# vme_bus_buff.net
KiCad netlist of a schematic drawn in Altium Designer
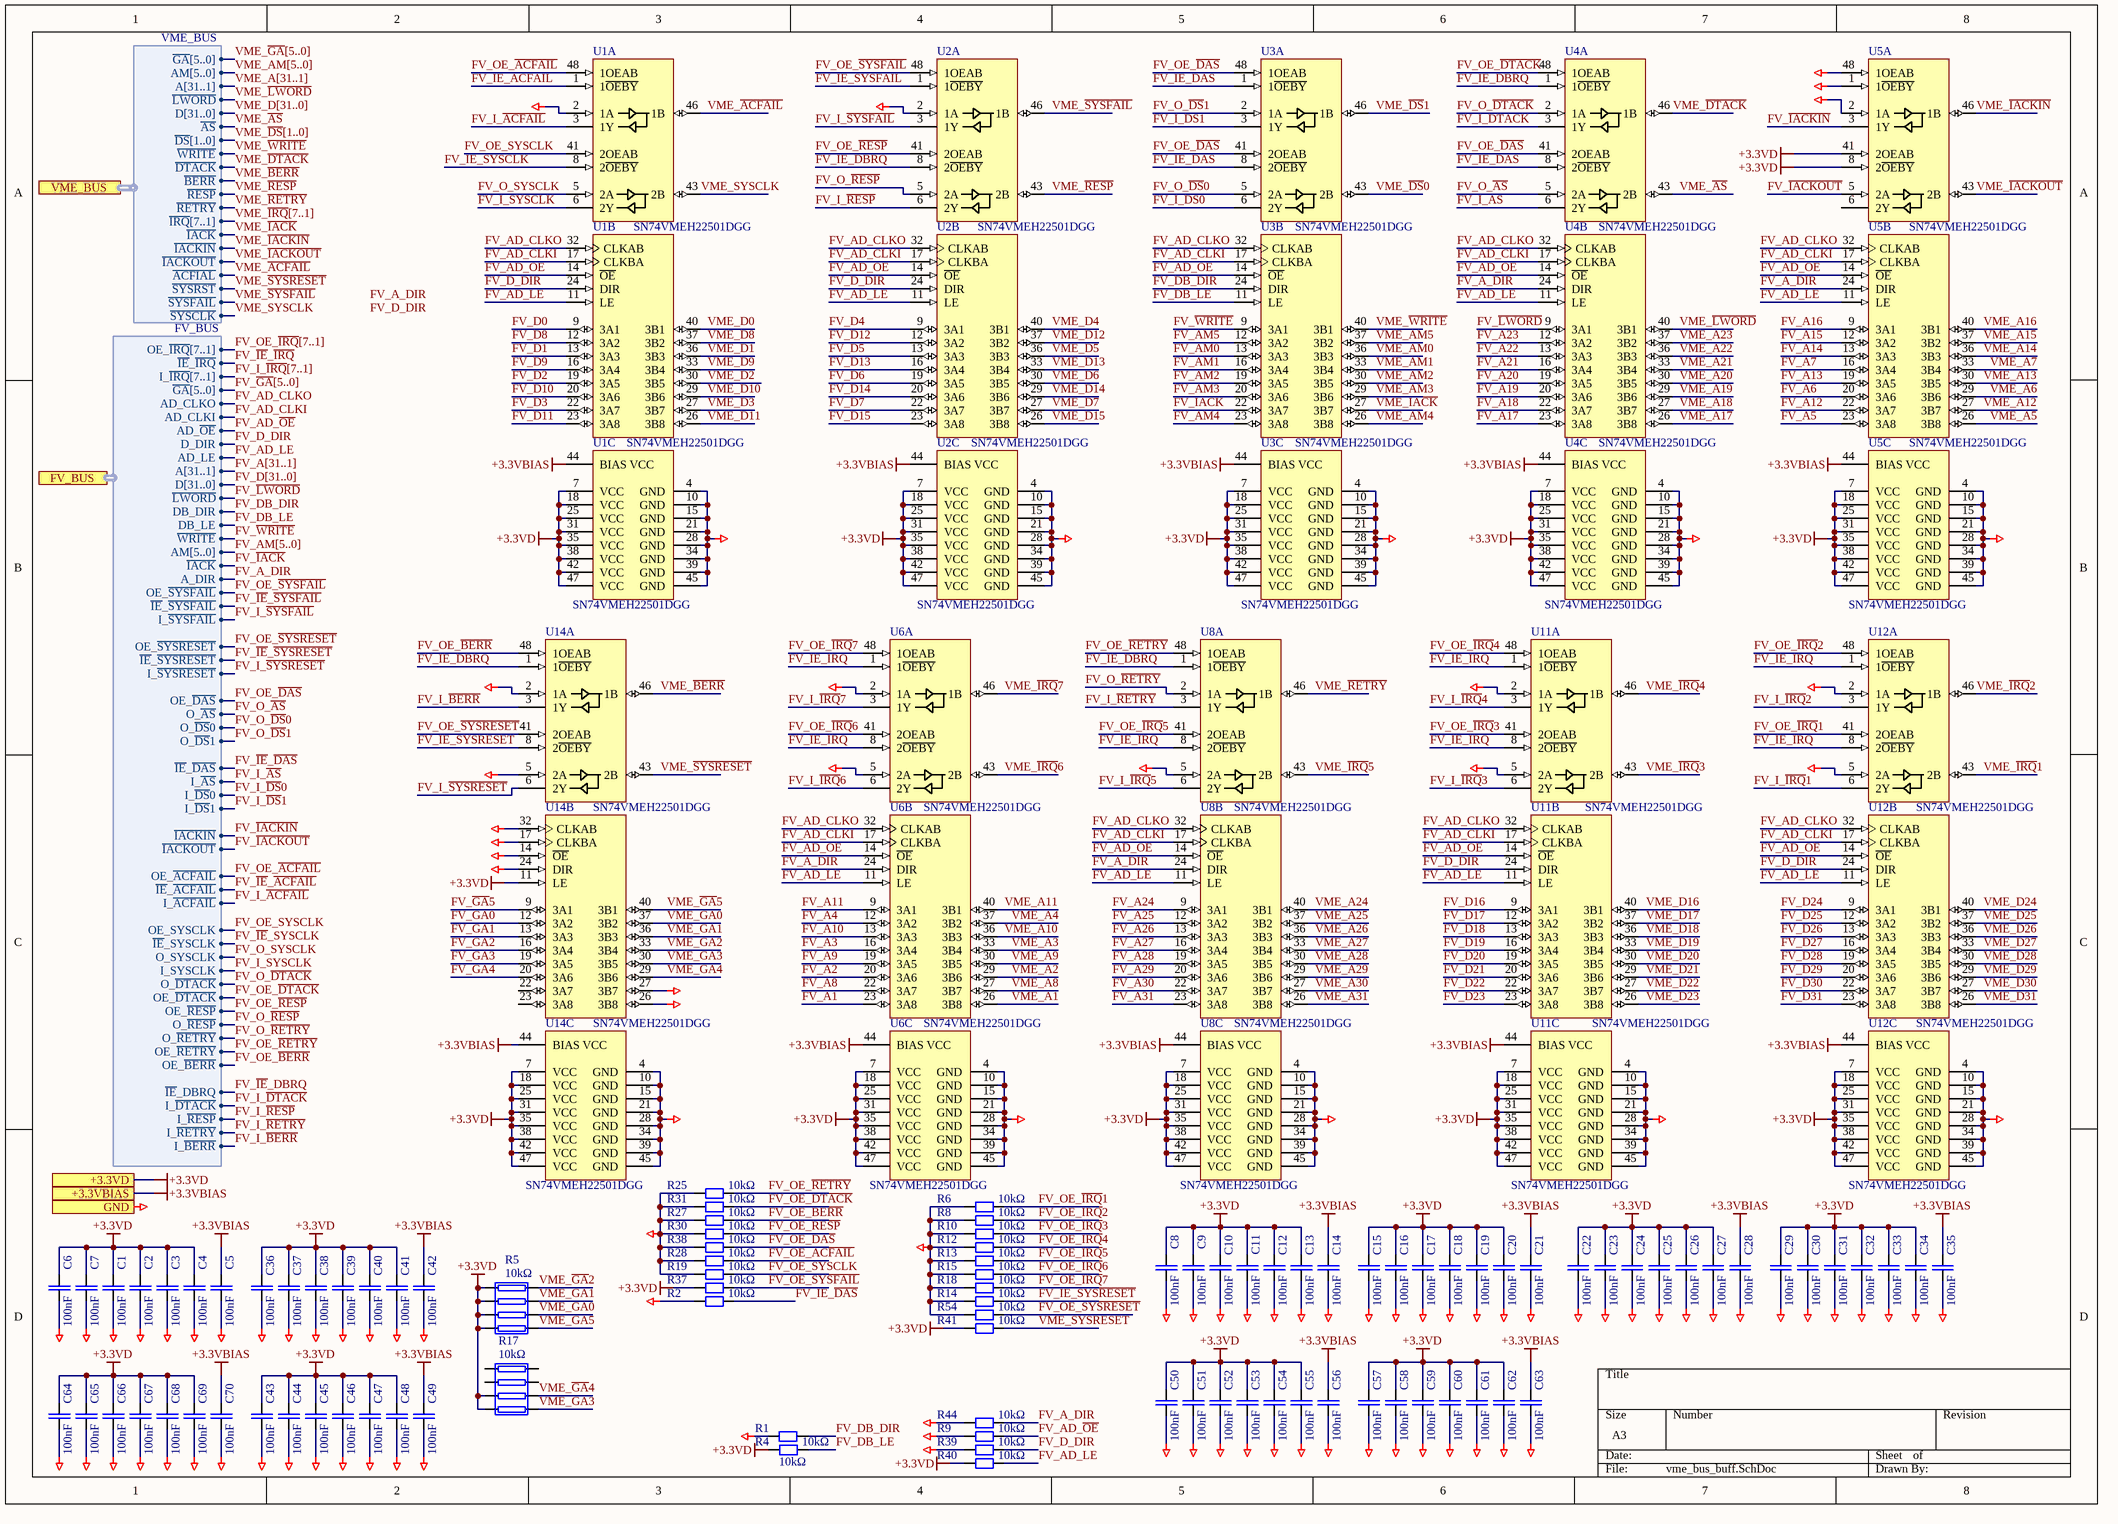
[diagram p0: vme_bus_buff.SchDoc]

(export (version "E")
  (design (tool "Eeschema 10.0.6"))
  (components
    (comp (ref "C1")
      (value "100nF")
      (footprint "CAPC1608N")
      (description "Generic ceramic SMD capacitor")
      (fields (field (name "MAINTAINER") "Evgeniy Kotov"))
      (libsource (lib "[Capacitors] Capacitors SMD") (part "CAPC"))
    )
    (comp (ref "C2")
      (value "100nF")
      (footprint "CAPC1608N")
      (description "Generic ceramic SMD capacitor")
      (fields (field (name "MAINTAINER") "Evgeniy Kotov"))
      (libsource (lib "[Capacitors] Capacitors SMD") (part "CAPC"))
    )
    (comp (ref "C3")
      (value "100nF")
      (footprint "CAPC1608N")
      (description "Generic ceramic SMD capacitor")
      (fields (field (name "MAINTAINER") "Evgeniy Kotov"))
      (libsource (lib "[Capacitors] Capacitors SMD") (part "CAPC"))
    )
    (comp (ref "C4")
      (value "100nF")
      (footprint "CAPC1608N")
      (description "Generic ceramic SMD capacitor")
      (fields (field (name "MAINTAINER") "Evgeniy Kotov"))
      (libsource (lib "[Capacitors] Capacitors SMD") (part "CAPC"))
    )
    (comp (ref "C5")
      (value "100nF")
      (footprint "CAPC1608N")
      (description "Generic ceramic SMD capacitor")
      (fields (field (name "MAINTAINER") "Evgeniy Kotov"))
      (libsource (lib "[Capacitors] Capacitors SMD") (part "CAPC"))
    )
    (comp (ref "C6")
      (value "100nF")
      (footprint "CAPC1608N")
      (description "Generic ceramic SMD capacitor")
      (fields (field (name "MAINTAINER") "Evgeniy Kotov"))
      (libsource (lib "[Capacitors] Capacitors SMD") (part "CAPC"))
    )
    (comp (ref "C7")
      (value "100nF")
      (footprint "CAPC1608N")
      (description "Generic ceramic SMD capacitor")
      (fields (field (name "MAINTAINER") "Evgeniy Kotov"))
      (libsource (lib "[Capacitors] Capacitors SMD") (part "CAPC"))
    )
    (comp (ref "C8")
      (value "100nF")
      (footprint "CAPC1608N")
      (description "Generic ceramic SMD capacitor")
      (fields (field (name "MAINTAINER") "Evgeniy Kotov"))
      (libsource (lib "[Capacitors] Capacitors SMD") (part "CAPC"))
    )
    (comp (ref "C9")
      (value "100nF")
      (footprint "CAPC1608N")
      (description "Generic ceramic SMD capacitor")
      (fields (field (name "MAINTAINER") "Evgeniy Kotov"))
      (libsource (lib "[Capacitors] Capacitors SMD") (part "CAPC"))
    )
    (comp (ref "C10")
      (value "100nF")
      (footprint "CAPC1608N")
      (description "Generic ceramic SMD capacitor")
      (fields (field (name "MAINTAINER") "Evgeniy Kotov"))
      (libsource (lib "[Capacitors] Capacitors SMD") (part "CAPC"))
    )
    (comp (ref "C11")
      (value "100nF")
      (footprint "CAPC1608N")
      (description "Generic ceramic SMD capacitor")
      (fields (field (name "MAINTAINER") "Evgeniy Kotov"))
      (libsource (lib "[Capacitors] Capacitors SMD") (part "CAPC"))
    )
    (comp (ref "C12")
      (value "100nF")
      (footprint "CAPC1608N")
      (description "Generic ceramic SMD capacitor")
      (fields (field (name "MAINTAINER") "Evgeniy Kotov"))
      (libsource (lib "[Capacitors] Capacitors SMD") (part "CAPC"))
    )
    (comp (ref "C13")
      (value "100nF")
      (footprint "CAPC1608N")
      (description "Generic ceramic SMD capacitor")
      (fields (field (name "MAINTAINER") "Evgeniy Kotov"))
      (libsource (lib "[Capacitors] Capacitors SMD") (part "CAPC"))
    )
    (comp (ref "C14")
      (value "100nF")
      (footprint "CAPC1608N")
      (description "Generic ceramic SMD capacitor")
      (fields (field (name "MAINTAINER") "Evgeniy Kotov"))
      (libsource (lib "[Capacitors] Capacitors SMD") (part "CAPC"))
    )
    (comp (ref "C15")
      (value "100nF")
      (footprint "CAPC1608N")
      (description "Generic ceramic SMD capacitor")
      (fields (field (name "MAINTAINER") "Evgeniy Kotov"))
      (libsource (lib "[Capacitors] Capacitors SMD") (part "CAPC"))
    )
    (comp (ref "C16")
      (value "100nF")
      (footprint "CAPC1608N")
      (description "Generic ceramic SMD capacitor")
      (fields (field (name "MAINTAINER") "Evgeniy Kotov"))
      (libsource (lib "[Capacitors] Capacitors SMD") (part "CAPC"))
    )
    (comp (ref "C17")
      (value "100nF")
      (footprint "CAPC1608N")
      (description "Generic ceramic SMD capacitor")
      (fields (field (name "MAINTAINER") "Evgeniy Kotov"))
      (libsource (lib "[Capacitors] Capacitors SMD") (part "CAPC"))
    )
    (comp (ref "C18")
      (value "100nF")
      (footprint "CAPC1608N")
      (description "Generic ceramic SMD capacitor")
      (fields (field (name "MAINTAINER") "Evgeniy Kotov"))
      (libsource (lib "[Capacitors] Capacitors SMD") (part "CAPC"))
    )
    (comp (ref "C19")
      (value "100nF")
      (footprint "CAPC1608N")
      (description "Generic ceramic SMD capacitor")
      (fields (field (name "MAINTAINER") "Evgeniy Kotov"))
      (libsource (lib "[Capacitors] Capacitors SMD") (part "CAPC"))
    )
    (comp (ref "C20")
      (value "100nF")
      (footprint "CAPC1608N")
      (description "Generic ceramic SMD capacitor")
      (fields (field (name "MAINTAINER") "Evgeniy Kotov"))
      (libsource (lib "[Capacitors] Capacitors SMD") (part "CAPC"))
    )
    (comp (ref "C21")
      (value "100nF")
      (footprint "CAPC1608N")
      (description "Generic ceramic SMD capacitor")
      (fields (field (name "MAINTAINER") "Evgeniy Kotov"))
      (libsource (lib "[Capacitors] Capacitors SMD") (part "CAPC"))
    )
    (comp (ref "C22")
      (value "100nF")
      (footprint "CAPC1608N")
      (description "Generic ceramic SMD capacitor")
      (fields (field (name "MAINTAINER") "Evgeniy Kotov"))
      (libsource (lib "[Capacitors] Capacitors SMD") (part "CAPC"))
    )
    (comp (ref "C23")
      (value "100nF")
      (footprint "CAPC1608N")
      (description "Generic ceramic SMD capacitor")
      (fields (field (name "MAINTAINER") "Evgeniy Kotov"))
      (libsource (lib "[Capacitors] Capacitors SMD") (part "CAPC"))
    )
    (comp (ref "C24")
      (value "100nF")
      (footprint "CAPC1608N")
      (description "Generic ceramic SMD capacitor")
      (fields (field (name "MAINTAINER") "Evgeniy Kotov"))
      (libsource (lib "[Capacitors] Capacitors SMD") (part "CAPC"))
    )
    (comp (ref "C25")
      (value "100nF")
      (footprint "CAPC1608N")
      (description "Generic ceramic SMD capacitor")
      (fields (field (name "MAINTAINER") "Evgeniy Kotov"))
      (libsource (lib "[Capacitors] Capacitors SMD") (part "CAPC"))
    )
    (comp (ref "C26")
      (value "100nF")
      (footprint "CAPC1608N")
      (description "Generic ceramic SMD capacitor")
      (fields (field (name "MAINTAINER") "Evgeniy Kotov"))
      (libsource (lib "[Capacitors] Capacitors SMD") (part "CAPC"))
    )
    (comp (ref "C27")
      (value "100nF")
      (footprint "CAPC1608N")
      (description "Generic ceramic SMD capacitor")
      (fields (field (name "MAINTAINER") "Evgeniy Kotov"))
      (libsource (lib "[Capacitors] Capacitors SMD") (part "CAPC"))
    )
    (comp (ref "C28")
      (value "100nF")
      (footprint "CAPC1608N")
      (description "Generic ceramic SMD capacitor")
      (fields (field (name "MAINTAINER") "Evgeniy Kotov"))
      (libsource (lib "[Capacitors] Capacitors SMD") (part "CAPC"))
    )
    (comp (ref "C29")
      (value "100nF")
      (footprint "CAPC1608N")
      (description "Generic ceramic SMD capacitor")
      (fields (field (name "MAINTAINER") "Evgeniy Kotov"))
      (libsource (lib "[Capacitors] Capacitors SMD") (part "CAPC"))
    )
    (comp (ref "C30")
      (value "100nF")
      (footprint "CAPC1608N")
      (description "Generic ceramic SMD capacitor")
      (fields (field (name "MAINTAINER") "Evgeniy Kotov"))
      (libsource (lib "[Capacitors] Capacitors SMD") (part "CAPC"))
    )
    (comp (ref "C31")
      (value "100nF")
      (footprint "CAPC1608N")
      (description "Generic ceramic SMD capacitor")
      (fields (field (name "MAINTAINER") "Evgeniy Kotov"))
      (libsource (lib "[Capacitors] Capacitors SMD") (part "CAPC"))
    )
    (comp (ref "C32")
      (value "100nF")
      (footprint "CAPC1608N")
      (description "Generic ceramic SMD capacitor")
      (fields (field (name "MAINTAINER") "Evgeniy Kotov"))
      (libsource (lib "[Capacitors] Capacitors SMD") (part "CAPC"))
    )
    (comp (ref "C33")
      (value "100nF")
      (footprint "CAPC1608N")
      (description "Generic ceramic SMD capacitor")
      (fields (field (name "MAINTAINER") "Evgeniy Kotov"))
      (libsource (lib "[Capacitors] Capacitors SMD") (part "CAPC"))
    )
    (comp (ref "C34")
      (value "100nF")
      (footprint "CAPC1608N")
      (description "Generic ceramic SMD capacitor")
      (fields (field (name "MAINTAINER") "Evgeniy Kotov"))
      (libsource (lib "[Capacitors] Capacitors SMD") (part "CAPC"))
    )
    (comp (ref "C35")
      (value "100nF")
      (footprint "CAPC1608N")
      (description "Generic ceramic SMD capacitor")
      (fields (field (name "MAINTAINER") "Evgeniy Kotov"))
      (libsource (lib "[Capacitors] Capacitors SMD") (part "CAPC"))
    )
    (comp (ref "C36")
      (value "100nF")
      (footprint "CAPC1608N")
      (description "Generic ceramic SMD capacitor")
      (fields (field (name "MAINTAINER") "Evgeniy Kotov"))
      (libsource (lib "[Capacitors] Capacitors SMD") (part "CAPC"))
    )
    (comp (ref "C37")
      (value "100nF")
      (footprint "CAPC1608N")
      (description "Generic ceramic SMD capacitor")
      (fields (field (name "MAINTAINER") "Evgeniy Kotov"))
      (libsource (lib "[Capacitors] Capacitors SMD") (part "CAPC"))
    )
    (comp (ref "C38")
      (value "100nF")
      (footprint "CAPC1608N")
      (description "Generic ceramic SMD capacitor")
      (fields (field (name "MAINTAINER") "Evgeniy Kotov"))
      (libsource (lib "[Capacitors] Capacitors SMD") (part "CAPC"))
    )
    (comp (ref "C39")
      (value "100nF")
      (footprint "CAPC1608N")
      (description "Generic ceramic SMD capacitor")
      (fields (field (name "MAINTAINER") "Evgeniy Kotov"))
      (libsource (lib "[Capacitors] Capacitors SMD") (part "CAPC"))
    )
    (comp (ref "C40")
      (value "100nF")
      (footprint "CAPC1608N")
      (description "Generic ceramic SMD capacitor")
      (fields (field (name "MAINTAINER") "Evgeniy Kotov"))
      (libsource (lib "[Capacitors] Capacitors SMD") (part "CAPC"))
    )
    (comp (ref "C41")
      (value "100nF")
      (footprint "CAPC1608N")
      (description "Generic ceramic SMD capacitor")
      (fields (field (name "MAINTAINER") "Evgeniy Kotov"))
      (libsource (lib "[Capacitors] Capacitors SMD") (part "CAPC"))
    )
    (comp (ref "C42")
      (value "100nF")
      (footprint "CAPC1608N")
      (description "Generic ceramic SMD capacitor")
      (fields (field (name "MAINTAINER") "Evgeniy Kotov"))
      (libsource (lib "[Capacitors] Capacitors SMD") (part "CAPC"))
    )
    (comp (ref "C43")
      (value "100nF")
      (footprint "CAPC1608N")
      (description "Generic ceramic SMD capacitor")
      (fields (field (name "MAINTAINER") "Evgeniy Kotov"))
      (libsource (lib "[Capacitors] Capacitors SMD") (part "CAPC"))
    )
    (comp (ref "C44")
      (value "100nF")
      (footprint "CAPC1608N")
      (description "Generic ceramic SMD capacitor")
      (fields (field (name "MAINTAINER") "Evgeniy Kotov"))
      (libsource (lib "[Capacitors] Capacitors SMD") (part "CAPC"))
    )
    (comp (ref "C45")
      (value "100nF")
      (footprint "CAPC1608N")
      (description "Generic ceramic SMD capacitor")
      (fields (field (name "MAINTAINER") "Evgeniy Kotov"))
      (libsource (lib "[Capacitors] Capacitors SMD") (part "CAPC"))
    )
    (comp (ref "C46")
      (value "100nF")
      (footprint "CAPC1608N")
      (description "Generic ceramic SMD capacitor")
      (fields (field (name "MAINTAINER") "Evgeniy Kotov"))
      (libsource (lib "[Capacitors] Capacitors SMD") (part "CAPC"))
    )
    (comp (ref "C47")
      (value "100nF")
      (footprint "CAPC1608N")
      (description "Generic ceramic SMD capacitor")
      (fields (field (name "MAINTAINER") "Evgeniy Kotov"))
      (libsource (lib "[Capacitors] Capacitors SMD") (part "CAPC"))
    )
    (comp (ref "C48")
      (value "100nF")
      (footprint "CAPC1608N")
      (description "Generic ceramic SMD capacitor")
      (fields (field (name "MAINTAINER") "Evgeniy Kotov"))
      (libsource (lib "[Capacitors] Capacitors SMD") (part "CAPC"))
    )
    (comp (ref "C49")
      (value "100nF")
      (footprint "CAPC1608N")
      (description "Generic ceramic SMD capacitor")
      (fields (field (name "MAINTAINER") "Evgeniy Kotov"))
      (libsource (lib "[Capacitors] Capacitors SMD") (part "CAPC"))
    )
    (comp (ref "C50")
      (value "100nF")
      (footprint "CAPC1608N")
      (description "Generic ceramic SMD capacitor")
      (fields (field (name "MAINTAINER") "Evgeniy Kotov"))
      (libsource (lib "[Capacitors] Capacitors SMD") (part "CAPC"))
    )
    (comp (ref "C51")
      (value "100nF")
      (footprint "CAPC1608N")
      (description "Generic ceramic SMD capacitor")
      (fields (field (name "MAINTAINER") "Evgeniy Kotov"))
      (libsource (lib "[Capacitors] Capacitors SMD") (part "CAPC"))
    )
    (comp (ref "C52")
      (value "100nF")
      (footprint "CAPC1608N")
      (description "Generic ceramic SMD capacitor")
      (fields (field (name "MAINTAINER") "Evgeniy Kotov"))
      (libsource (lib "[Capacitors] Capacitors SMD") (part "CAPC"))
    )
    (comp (ref "C53")
      (value "100nF")
      (footprint "CAPC1608N")
      (description "Generic ceramic SMD capacitor")
      (fields (field (name "MAINTAINER") "Evgeniy Kotov"))
      (libsource (lib "[Capacitors] Capacitors SMD") (part "CAPC"))
    )
    (comp (ref "C54")
      (value "100nF")
      (footprint "CAPC1608N")
      (description "Generic ceramic SMD capacitor")
      (fields (field (name "MAINTAINER") "Evgeniy Kotov"))
      (libsource (lib "[Capacitors] Capacitors SMD") (part "CAPC"))
    )
    (comp (ref "C55")
      (value "100nF")
      (footprint "CAPC1608N")
      (description "Generic ceramic SMD capacitor")
      (fields (field (name "MAINTAINER") "Evgeniy Kotov"))
      (libsource (lib "[Capacitors] Capacitors SMD") (part "CAPC"))
    )
    (comp (ref "C56")
      (value "100nF")
      (footprint "CAPC1608N")
      (description "Generic ceramic SMD capacitor")
      (fields (field (name "MAINTAINER") "Evgeniy Kotov"))
      (libsource (lib "[Capacitors] Capacitors SMD") (part "CAPC"))
    )
    (comp (ref "C57")
      (value "100nF")
      (footprint "CAPC1608N")
      (description "Generic ceramic SMD capacitor")
      (fields (field (name "MAINTAINER") "Evgeniy Kotov"))
      (libsource (lib "[Capacitors] Capacitors SMD") (part "CAPC"))
    )
    (comp (ref "C58")
      (value "100nF")
      (footprint "CAPC1608N")
      (description "Generic ceramic SMD capacitor")
      (fields (field (name "MAINTAINER") "Evgeniy Kotov"))
      (libsource (lib "[Capacitors] Capacitors SMD") (part "CAPC"))
    )
    (comp (ref "C59")
      (value "100nF")
      (footprint "CAPC1608N")
      (description "Generic ceramic SMD capacitor")
      (fields (field (name "MAINTAINER") "Evgeniy Kotov"))
      (libsource (lib "[Capacitors] Capacitors SMD") (part "CAPC"))
    )
    (comp (ref "C60")
      (value "100nF")
      (footprint "CAPC1608N")
      (description "Generic ceramic SMD capacitor")
      (fields (field (name "MAINTAINER") "Evgeniy Kotov"))
      (libsource (lib "[Capacitors] Capacitors SMD") (part "CAPC"))
    )
    (comp (ref "C61")
      (value "100nF")
      (footprint "CAPC1608N")
      (description "Generic ceramic SMD capacitor")
      (fields (field (name "MAINTAINER") "Evgeniy Kotov"))
      (libsource (lib "[Capacitors] Capacitors SMD") (part "CAPC"))
    )
    (comp (ref "C62")
      (value "100nF")
      (footprint "CAPC1608N")
      (description "Generic ceramic SMD capacitor")
      (fields (field (name "MAINTAINER") "Evgeniy Kotov"))
      (libsource (lib "[Capacitors] Capacitors SMD") (part "CAPC"))
    )
    (comp (ref "C63")
      (value "100nF")
      (footprint "CAPC1608N")
      (description "Generic ceramic SMD capacitor")
      (fields (field (name "MAINTAINER") "Evgeniy Kotov"))
      (libsource (lib "[Capacitors] Capacitors SMD") (part "CAPC"))
    )
    (comp (ref "C64")
      (value "100nF")
      (footprint "CAPC1608N")
      (description "Generic ceramic SMD capacitor")
      (fields (field (name "MAINTAINER") "Evgeniy Kotov"))
      (libsource (lib "[Capacitors] Capacitors SMD") (part "CAPC"))
    )
    (comp (ref "C65")
      (value "100nF")
      (footprint "CAPC1608N")
      (description "Generic ceramic SMD capacitor")
      (fields (field (name "MAINTAINER") "Evgeniy Kotov"))
      (libsource (lib "[Capacitors] Capacitors SMD") (part "CAPC"))
    )
    (comp (ref "C66")
      (value "100nF")
      (footprint "CAPC1608N")
      (description "Generic ceramic SMD capacitor")
      (fields (field (name "MAINTAINER") "Evgeniy Kotov"))
      (libsource (lib "[Capacitors] Capacitors SMD") (part "CAPC"))
    )
    (comp (ref "C67")
      (value "100nF")
      (footprint "CAPC1608N")
      (description "Generic ceramic SMD capacitor")
      (fields (field (name "MAINTAINER") "Evgeniy Kotov"))
      (libsource (lib "[Capacitors] Capacitors SMD") (part "CAPC"))
    )
    (comp (ref "C68")
      (value "100nF")
      (footprint "CAPC1608N")
      (description "Generic ceramic SMD capacitor")
      (fields (field (name "MAINTAINER") "Evgeniy Kotov"))
      (libsource (lib "[Capacitors] Capacitors SMD") (part "CAPC"))
    )
    (comp (ref "C69")
      (value "100nF")
      (footprint "CAPC1608N")
      (description "Generic ceramic SMD capacitor")
      (fields (field (name "MAINTAINER") "Evgeniy Kotov"))
      (libsource (lib "[Capacitors] Capacitors SMD") (part "CAPC"))
    )
    (comp (ref "C70")
      (value "100nF")
      (footprint "CAPC1608N")
      (description "Generic ceramic SMD capacitor")
      (fields (field (name "MAINTAINER") "Evgeniy Kotov"))
      (libsource (lib "[Capacitors] Capacitors SMD") (part "CAPC"))
    )
    (comp (ref "R1")
      (value "10kΩ")
      (footprint "RESC2012N")
      (description "Resistor, Generic, SMD")
      (fields (field (name "MAINTAINER") "Evgeniy Kotov"))
      (libsource (lib "[Resistors] Resistors SMD") (part "RESC"))
    )
    (comp (ref "R2")
      (value "10kΩ")
      (footprint "RESC2012N")
      (description "Resistor, Generic, SMD")
      (fields (field (name "MAINTAINER") "Evgeniy Kotov"))
      (libsource (lib "[Resistors] Resistors SMD") (part "RESC"))
    )
    (comp (ref "R4")
      (value "10kΩ")
      (footprint "RESC2012N")
      (description "Resistor, Generic, SMD")
      (fields (field (name "MAINTAINER") "Evgeniy Kotov"))
      (libsource (lib "[Resistors] Resistors SMD") (part "RESC"))
    )
    (comp (ref "R5")
      (value "10kΩ")
      (footprint "CAY16-J4")
      (fields (field (name "Comment") "CAY16-1002F4LF") (field (name "MAINTAINER") "Anton Pavlenko"))
      (libsource (lib "[Resistors] Resistors SMD") (part "RESPACK4"))
    )
    (comp (ref "R6")
      (value "10kΩ")
      (footprint "RESC2012N")
      (description "Resistor, Generic, SMD")
      (fields (field (name "MAINTAINER") "Evgeniy Kotov"))
      (libsource (lib "[Resistors] Resistors SMD") (part "RESC"))
    )
    (comp (ref "R8")
      (value "10kΩ")
      (footprint "RESC2012N")
      (description "Resistor, Generic, SMD")
      (fields (field (name "MAINTAINER") "Evgeniy Kotov"))
      (libsource (lib "[Resistors] Resistors SMD") (part "RESC"))
    )
    (comp (ref "R9")
      (value "10kΩ")
      (footprint "RESC2012N")
      (description "Resistor, Generic, SMD")
      (fields (field (name "MAINTAINER") "Evgeniy Kotov"))
      (libsource (lib "[Resistors] Resistors SMD") (part "RESC"))
    )
    (comp (ref "R10")
      (value "10kΩ")
      (footprint "RESC2012N")
      (description "Resistor, Generic, SMD")
      (fields (field (name "MAINTAINER") "Evgeniy Kotov"))
      (libsource (lib "[Resistors] Resistors SMD") (part "RESC"))
    )
    (comp (ref "R12")
      (value "10kΩ")
      (footprint "RESC2012N")
      (description "Resistor, Generic, SMD")
      (fields (field (name "MAINTAINER") "Evgeniy Kotov"))
      (libsource (lib "[Resistors] Resistors SMD") (part "RESC"))
    )
    (comp (ref "R13")
      (value "10kΩ")
      (footprint "RESC2012N")
      (description "Resistor, Generic, SMD")
      (fields (field (name "MAINTAINER") "Evgeniy Kotov"))
      (libsource (lib "[Resistors] Resistors SMD") (part "RESC"))
    )
    (comp (ref "R14")
      (value "10kΩ")
      (footprint "RESC2012N")
      (description "Resistor, Generic, SMD")
      (fields (field (name "MAINTAINER") "Evgeniy Kotov"))
      (libsource (lib "[Resistors] Resistors SMD") (part "RESC"))
    )
    (comp (ref "R15")
      (value "10kΩ")
      (footprint "RESC2012N")
      (description "Resistor, Generic, SMD")
      (fields (field (name "MAINTAINER") "Evgeniy Kotov"))
      (libsource (lib "[Resistors] Resistors SMD") (part "RESC"))
    )
    (comp (ref "R17")
      (value "10kΩ")
      (footprint "CAY16-J4")
      (fields (field (name "Comment") "CAY16-1002F4LF") (field (name "MAINTAINER") "Anton Pavlenko"))
      (libsource (lib "[Resistors] Resistors SMD") (part "RESPACK4"))
    )
    (comp (ref "R18")
      (value "10kΩ")
      (footprint "RESC2012N")
      (description "Resistor, Generic, SMD")
      (fields (field (name "MAINTAINER") "Evgeniy Kotov"))
      (libsource (lib "[Resistors] Resistors SMD") (part "RESC"))
    )
    (comp (ref "R19")
      (value "10kΩ")
      (footprint "RESC2012N")
      (description "Resistor, Generic, SMD")
      (fields (field (name "MAINTAINER") "Evgeniy Kotov"))
      (libsource (lib "[Resistors] Resistors SMD") (part "RESC"))
    )
    (comp (ref "R25")
      (value "10kΩ")
      (footprint "RESC2012N")
      (description "Resistor, Generic, SMD")
      (fields (field (name "MAINTAINER") "Evgeniy Kotov"))
      (libsource (lib "[Resistors] Resistors SMD") (part "RESC"))
    )
    (comp (ref "R27")
      (value "10kΩ")
      (footprint "RESC2012N")
      (description "Resistor, Generic, SMD")
      (fields (field (name "MAINTAINER") "Evgeniy Kotov"))
      (libsource (lib "[Resistors] Resistors SMD") (part "RESC"))
    )
    (comp (ref "R28")
      (value "10kΩ")
      (footprint "RESC2012N")
      (description "Resistor, Generic, SMD")
      (fields (field (name "MAINTAINER") "Evgeniy Kotov"))
      (libsource (lib "[Resistors] Resistors SMD") (part "RESC"))
    )
    (comp (ref "R30")
      (value "10kΩ")
      (footprint "RESC2012N")
      (description "Resistor, Generic, SMD")
      (fields (field (name "MAINTAINER") "Evgeniy Kotov"))
      (libsource (lib "[Resistors] Resistors SMD") (part "RESC"))
    )
    (comp (ref "R31")
      (value "10kΩ")
      (footprint "RESC2012N")
      (description "Resistor, Generic, SMD")
      (fields (field (name "MAINTAINER") "Evgeniy Kotov"))
      (libsource (lib "[Resistors] Resistors SMD") (part "RESC"))
    )
    (comp (ref "R37")
      (value "10kΩ")
      (footprint "RESC2012N")
      (description "Resistor, Generic, SMD")
      (fields (field (name "MAINTAINER") "Evgeniy Kotov"))
      (libsource (lib "[Resistors] Resistors SMD") (part "RESC"))
    )
    (comp (ref "R38")
      (value "10kΩ")
      (footprint "RESC2012N")
      (description "Resistor, Generic, SMD")
      (fields (field (name "MAINTAINER") "Evgeniy Kotov"))
      (libsource (lib "[Resistors] Resistors SMD") (part "RESC"))
    )
    (comp (ref "R39")
      (value "10kΩ")
      (footprint "RESC2012N")
      (description "Resistor, Generic, SMD")
      (fields (field (name "MAINTAINER") "Evgeniy Kotov"))
      (libsource (lib "[Resistors] Resistors SMD") (part "RESC"))
    )
    (comp (ref "R40")
      (value "10kΩ")
      (footprint "RESC2012N")
      (description "Resistor, Generic, SMD")
      (fields (field (name "MAINTAINER") "Evgeniy Kotov"))
      (libsource (lib "[Resistors] Resistors SMD") (part "RESC"))
    )
    (comp (ref "R41")
      (value "10kΩ")
      (footprint "RESC2012N")
      (description "Resistor, Generic, SMD")
      (fields (field (name "MAINTAINER") "Evgeniy Kotov"))
      (libsource (lib "[Resistors] Resistors SMD") (part "RESC"))
    )
    (comp (ref "R44")
      (value "10kΩ")
      (footprint "RESC2012N")
      (description "Resistor, Generic, SMD")
      (fields (field (name "MAINTAINER") "Evgeniy Kotov"))
      (libsource (lib "[Resistors] Resistors SMD") (part "RESC"))
    )
    (comp (ref "R54")
      (value "10kΩ")
      (footprint "RESC2012N")
      (description "Resistor, Generic, SMD")
      (fields (field (name "MAINTAINER") "Evgeniy Kotov"))
      (libsource (lib "[Resistors] Resistors SMD") (part "RESC"))
    )
    (comp (ref "U1")
      (value "SN74VMEH22501DGG")
      (footprint "DGG0048A_L")
      (fields
        (field (name "MANUFACTURER") "Texas Instruments")
        (field (name "GENERIC PART NUMBER") "SN74VMEH22501")
      )
      (libsource (lib "LogicIC") (part "TI-SN74VMEH22501DGG"))
    )
    (comp (ref "U2")
      (value "SN74VMEH22501DGG")
      (footprint "DGG0048A_L")
      (fields
        (field (name "MANUFACTURER") "Texas Instruments")
        (field (name "GENERIC PART NUMBER") "SN74VMEH22501")
      )
      (libsource (lib "LogicIC") (part "TI-SN74VMEH22501DGG"))
    )
    (comp (ref "U3")
      (value "SN74VMEH22501DGG")
      (footprint "DGG0048A_L")
      (fields
        (field (name "MANUFACTURER") "Texas Instruments")
        (field (name "GENERIC PART NUMBER") "SN74VMEH22501")
      )
      (libsource (lib "LogicIC") (part "TI-SN74VMEH22501DGG"))
    )
    (comp (ref "U4")
      (value "SN74VMEH22501DGG")
      (footprint "DGG0048A_L")
      (fields
        (field (name "MANUFACTURER") "Texas Instruments")
        (field (name "GENERIC PART NUMBER") "SN74VMEH22501")
      )
      (libsource (lib "LogicIC") (part "TI-SN74VMEH22501DGG"))
    )
    (comp (ref "U5")
      (value "SN74VMEH22501DGG")
      (footprint "DGG0048A_L")
      (fields
        (field (name "MANUFACTURER") "Texas Instruments")
        (field (name "GENERIC PART NUMBER") "SN74VMEH22501")
      )
      (libsource (lib "LogicIC") (part "TI-SN74VMEH22501DGG"))
    )
    (comp (ref "U6")
      (value "SN74VMEH22501DGG")
      (footprint "DGG0048A_L")
      (fields
        (field (name "MANUFACTURER") "Texas Instruments")
        (field (name "GENERIC PART NUMBER") "SN74VMEH22501")
      )
      (libsource (lib "LogicIC") (part "TI-SN74VMEH22501DGG"))
    )
    (comp (ref "U8")
      (value "SN74VMEH22501DGG")
      (footprint "DGG0048A_L")
      (fields
        (field (name "MANUFACTURER") "Texas Instruments")
        (field (name "GENERIC PART NUMBER") "SN74VMEH22501")
      )
      (libsource (lib "LogicIC") (part "TI-SN74VMEH22501DGG"))
    )
    (comp (ref "U11")
      (value "SN74VMEH22501DGG")
      (footprint "DGG0048A_L")
      (fields
        (field (name "MANUFACTURER") "Texas Instruments")
        (field (name "GENERIC PART NUMBER") "SN74VMEH22501")
      )
      (libsource (lib "LogicIC") (part "TI-SN74VMEH22501DGG"))
    )
    (comp (ref "U12")
      (value "SN74VMEH22501DGG")
      (footprint "DGG0048A_L")
      (fields
        (field (name "MANUFACTURER") "Texas Instruments")
        (field (name "GENERIC PART NUMBER") "SN74VMEH22501")
      )
      (libsource (lib "LogicIC") (part "TI-SN74VMEH22501DGG"))
    )
    (comp (ref "U14")
      (value "SN74VMEH22501DGG")
      (footprint "DGG0048A_L")
      (fields
        (field (name "MANUFACTURER") "Texas Instruments")
        (field (name "GENERIC PART NUMBER") "SN74VMEH22501")
      )
      (libsource (lib "LogicIC") (part "TI-SN74VMEH22501DGG"))
    )
  )
  (nets
    (net (code "3") (name "+3.3VBIAS") (class "Default")
      (node (ref "C14") (pin "2") (pintype "passive"))
      (node (ref "C21") (pin "2") (pintype "passive"))
      (node (ref "C28") (pin "2") (pintype "passive"))
      (node (ref "C35") (pin "2") (pintype "passive"))
      (node (ref "C42") (pin "2") (pintype "passive"))
      (node (ref "C49") (pin "2") (pintype "passive"))
      (node (ref "C5") (pin "2") (pintype "passive"))
      (node (ref "C56") (pin "2") (pintype "passive"))
      (node (ref "C63") (pin "2") (pintype "passive"))
      (node (ref "C70") (pin "2") (pintype "passive"))
      (node (ref "U1") (pin "44") (pinfunction "BIAS_VCC_44") (pintype "power_in"))
      (node (ref "U11") (pin "44") (pinfunction "BIAS_VCC_44") (pintype "power_in"))
      (node (ref "U12") (pin "44") (pinfunction "BIAS_VCC_44") (pintype "power_in"))
      (node (ref "U14") (pin "44") (pinfunction "BIAS_VCC_44") (pintype "power_in"))
      (node (ref "U2") (pin "44") (pinfunction "BIAS_VCC_44") (pintype "power_in"))
      (node (ref "U3") (pin "44") (pinfunction "BIAS_VCC_44") (pintype "power_in"))
      (node (ref "U4") (pin "44") (pinfunction "BIAS_VCC_44") (pintype "power_in"))
      (node (ref "U5") (pin "44") (pinfunction "BIAS_VCC_44") (pintype "power_in"))
      (node (ref "U6") (pin "44") (pinfunction "BIAS_VCC_44") (pintype "power_in"))
      (node (ref "U8") (pin "44") (pinfunction "BIAS_VCC_44") (pintype "power_in"))
    )
    (net (code "4") (name "+3.3VD") (class "Default")
      (node (ref "C1") (pin "2") (pintype "passive"))
      (node (ref "C10") (pin "2") (pintype "passive"))
      (node (ref "C11") (pin "2") (pintype "passive"))
      (node (ref "C12") (pin "2") (pintype "passive"))
      (node (ref "C13") (pin "2") (pintype "passive"))
      (node (ref "C15") (pin "2") (pintype "passive"))
      (node (ref "C16") (pin "2") (pintype "passive"))
      (node (ref "C17") (pin "2") (pintype "passive"))
      (node (ref "C18") (pin "2") (pintype "passive"))
      (node (ref "C19") (pin "2") (pintype "passive"))
      (node (ref "C2") (pin "2") (pintype "passive"))
      (node (ref "C20") (pin "2") (pintype "passive"))
      (node (ref "C22") (pin "2") (pintype "passive"))
      (node (ref "C23") (pin "2") (pintype "passive"))
      (node (ref "C24") (pin "2") (pintype "passive"))
      (node (ref "C25") (pin "2") (pintype "passive"))
      (node (ref "C26") (pin "2") (pintype "passive"))
      (node (ref "C27") (pin "2") (pintype "passive"))
      (node (ref "C29") (pin "2") (pintype "passive"))
      (node (ref "C3") (pin "2") (pintype "passive"))
      (node (ref "C30") (pin "2") (pintype "passive"))
      (node (ref "C31") (pin "2") (pintype "passive"))
      (node (ref "C32") (pin "2") (pintype "passive"))
      (node (ref "C33") (pin "2") (pintype "passive"))
      (node (ref "C34") (pin "2") (pintype "passive"))
      (node (ref "C36") (pin "2") (pintype "passive"))
      (node (ref "C37") (pin "2") (pintype "passive"))
      (node (ref "C38") (pin "2") (pintype "passive"))
      (node (ref "C39") (pin "2") (pintype "passive"))
      (node (ref "C4") (pin "2") (pintype "passive"))
      (node (ref "C40") (pin "2") (pintype "passive"))
      (node (ref "C41") (pin "2") (pintype "passive"))
      (node (ref "C43") (pin "2") (pintype "passive"))
      (node (ref "C44") (pin "2") (pintype "passive"))
      (node (ref "C45") (pin "2") (pintype "passive"))
      (node (ref "C46") (pin "2") (pintype "passive"))
      (node (ref "C47") (pin "2") (pintype "passive"))
      (node (ref "C48") (pin "2") (pintype "passive"))
      (node (ref "C50") (pin "2") (pintype "passive"))
      (node (ref "C51") (pin "2") (pintype "passive"))
      (node (ref "C52") (pin "2") (pintype "passive"))
      (node (ref "C53") (pin "2") (pintype "passive"))
      (node (ref "C54") (pin "2") (pintype "passive"))
      (node (ref "C55") (pin "2") (pintype "passive"))
      (node (ref "C57") (pin "2") (pintype "passive"))
      (node (ref "C58") (pin "2") (pintype "passive"))
      (node (ref "C59") (pin "2") (pintype "passive"))
      (node (ref "C6") (pin "2") (pintype "passive"))
      (node (ref "C60") (pin "2") (pintype "passive"))
      (node (ref "C61") (pin "2") (pintype "passive"))
      (node (ref "C62") (pin "2") (pintype "passive"))
      (node (ref "C64") (pin "2") (pintype "passive"))
      (node (ref "C65") (pin "2") (pintype "passive"))
      (node (ref "C66") (pin "2") (pintype "passive"))
      (node (ref "C67") (pin "2") (pintype "passive"))
      (node (ref "C68") (pin "2") (pintype "passive"))
      (node (ref "C69") (pin "2") (pintype "passive"))
      (node (ref "C7") (pin "2") (pintype "passive"))
      (node (ref "C8") (pin "2") (pintype "passive"))
      (node (ref "C9") (pin "2") (pintype "passive"))
      (node (ref "R17") (pin "3") (pinfunction "3_3") (pintype "passive"))
      (node (ref "R17") (pin "4") (pinfunction "4_4") (pintype "passive"))
      (node (ref "R37") (pin "1") (pintype "passive"))
      (node (ref "R4") (pin "1") (pintype "passive"))
      (node (ref "R40") (pin "1") (pintype "passive"))
      (node (ref "R41") (pin "1") (pintype "passive"))
      (node (ref "R5") (pin "1") (pinfunction "1_1") (pintype "passive"))
      (node (ref "R5") (pin "2") (pinfunction "2_2") (pintype "passive"))
      (node (ref "R5") (pin "3") (pinfunction "3_3") (pintype "passive"))
      (node (ref "R5") (pin "4") (pinfunction "4_4") (pintype "passive"))
      (node (ref "U1") (pin "18") (pinfunction "VCC_18") (pintype "power_in"))
      (node (ref "U1") (pin "25") (pinfunction "VCC_25") (pintype "power_in"))
      (node (ref "U1") (pin "31") (pinfunction "VCC_31") (pintype "power_in"))
      (node (ref "U1") (pin "35") (pinfunction "VCC_35") (pintype "power_in"))
      (node (ref "U1") (pin "38") (pinfunction "VCC_38") (pintype "power_in"))
      (node (ref "U1") (pin "42") (pinfunction "VCC_42") (pintype "power_in"))
      (node (ref "U1") (pin "47") (pinfunction "VCC_47") (pintype "power_in"))
      (node (ref "U1") (pin "7") (pinfunction "VCC_7") (pintype "power_in"))
      (node (ref "U11") (pin "18") (pinfunction "VCC_18") (pintype "power_in"))
      (node (ref "U11") (pin "25") (pinfunction "VCC_25") (pintype "power_in"))
      (node (ref "U11") (pin "31") (pinfunction "VCC_31") (pintype "power_in"))
      (node (ref "U11") (pin "35") (pinfunction "VCC_35") (pintype "power_in"))
      (node (ref "U11") (pin "38") (pinfunction "VCC_38") (pintype "power_in"))
      (node (ref "U11") (pin "42") (pinfunction "VCC_42") (pintype "power_in"))
      (node (ref "U11") (pin "47") (pinfunction "VCC_47") (pintype "power_in"))
      (node (ref "U11") (pin "7") (pinfunction "VCC_7") (pintype "power_in"))
      (node (ref "U12") (pin "18") (pinfunction "VCC_18") (pintype "power_in"))
      (node (ref "U12") (pin "25") (pinfunction "VCC_25") (pintype "power_in"))
      (node (ref "U12") (pin "31") (pinfunction "VCC_31") (pintype "power_in"))
      (node (ref "U12") (pin "35") (pinfunction "VCC_35") (pintype "power_in"))
      (node (ref "U12") (pin "38") (pinfunction "VCC_38") (pintype "power_in"))
      (node (ref "U12") (pin "42") (pinfunction "VCC_42") (pintype "power_in"))
      (node (ref "U12") (pin "47") (pinfunction "VCC_47") (pintype "power_in"))
      (node (ref "U12") (pin "7") (pinfunction "VCC_7") (pintype "power_in"))
      (node (ref "U14") (pin "11") (pinfunction "LE_11") (pintype "input"))
      (node (ref "U14") (pin "18") (pinfunction "VCC_18") (pintype "power_in"))
      (node (ref "U14") (pin "25") (pinfunction "VCC_25") (pintype "power_in"))
      (node (ref "U14") (pin "31") (pinfunction "VCC_31") (pintype "power_in"))
      (node (ref "U14") (pin "35") (pinfunction "VCC_35") (pintype "power_in"))
      (node (ref "U14") (pin "38") (pinfunction "VCC_38") (pintype "power_in"))
      (node (ref "U14") (pin "42") (pinfunction "VCC_42") (pintype "power_in"))
      (node (ref "U14") (pin "47") (pinfunction "VCC_47") (pintype "power_in"))
      (node (ref "U14") (pin "7") (pinfunction "VCC_7") (pintype "power_in"))
      (node (ref "U2") (pin "18") (pinfunction "VCC_18") (pintype "power_in"))
      (node (ref "U2") (pin "25") (pinfunction "VCC_25") (pintype "power_in"))
      (node (ref "U2") (pin "31") (pinfunction "VCC_31") (pintype "power_in"))
      (node (ref "U2") (pin "35") (pinfunction "VCC_35") (pintype "power_in"))
      (node (ref "U2") (pin "38") (pinfunction "VCC_38") (pintype "power_in"))
      (node (ref "U2") (pin "42") (pinfunction "VCC_42") (pintype "power_in"))
      (node (ref "U2") (pin "47") (pinfunction "VCC_47") (pintype "power_in"))
      (node (ref "U2") (pin "7") (pinfunction "VCC_7") (pintype "power_in"))
      (node (ref "U3") (pin "18") (pinfunction "VCC_18") (pintype "power_in"))
      (node (ref "U3") (pin "25") (pinfunction "VCC_25") (pintype "power_in"))
      (node (ref "U3") (pin "31") (pinfunction "VCC_31") (pintype "power_in"))
      (node (ref "U3") (pin "35") (pinfunction "VCC_35") (pintype "power_in"))
      (node (ref "U3") (pin "38") (pinfunction "VCC_38") (pintype "power_in"))
      (node (ref "U3") (pin "42") (pinfunction "VCC_42") (pintype "power_in"))
      (node (ref "U3") (pin "47") (pinfunction "VCC_47") (pintype "power_in"))
      (node (ref "U3") (pin "7") (pinfunction "VCC_7") (pintype "power_in"))
      (node (ref "U4") (pin "18") (pinfunction "VCC_18") (pintype "power_in"))
      (node (ref "U4") (pin "25") (pinfunction "VCC_25") (pintype "power_in"))
      (node (ref "U4") (pin "31") (pinfunction "VCC_31") (pintype "power_in"))
      (node (ref "U4") (pin "35") (pinfunction "VCC_35") (pintype "power_in"))
      (node (ref "U4") (pin "38") (pinfunction "VCC_38") (pintype "power_in"))
      (node (ref "U4") (pin "42") (pinfunction "VCC_42") (pintype "power_in"))
      (node (ref "U4") (pin "47") (pinfunction "VCC_47") (pintype "power_in"))
      (node (ref "U4") (pin "7") (pinfunction "VCC_7") (pintype "power_in"))
      (node (ref "U5") (pin "18") (pinfunction "VCC_18") (pintype "power_in"))
      (node (ref "U5") (pin "25") (pinfunction "VCC_25") (pintype "power_in"))
      (node (ref "U5") (pin "31") (pinfunction "VCC_31") (pintype "power_in"))
      (node (ref "U5") (pin "35") (pinfunction "VCC_35") (pintype "power_in"))
      (node (ref "U5") (pin "38") (pinfunction "VCC_38") (pintype "power_in"))
      (node (ref "U5") (pin "41") (pinfunction "2OEAB_41") (pintype "input"))
      (node (ref "U5") (pin "42") (pinfunction "VCC_42") (pintype "power_in"))
      (node (ref "U5") (pin "47") (pinfunction "VCC_47") (pintype "power_in"))
      (node (ref "U5") (pin "7") (pinfunction "VCC_7") (pintype "power_in"))
      (node (ref "U5") (pin "8") (pinfunction "2~{OEBY}_8") (pintype "input"))
      (node (ref "U6") (pin "18") (pinfunction "VCC_18") (pintype "power_in"))
      (node (ref "U6") (pin "25") (pinfunction "VCC_25") (pintype "power_in"))
      (node (ref "U6") (pin "31") (pinfunction "VCC_31") (pintype "power_in"))
      (node (ref "U6") (pin "35") (pinfunction "VCC_35") (pintype "power_in"))
      (node (ref "U6") (pin "38") (pinfunction "VCC_38") (pintype "power_in"))
      (node (ref "U6") (pin "42") (pinfunction "VCC_42") (pintype "power_in"))
      (node (ref "U6") (pin "47") (pinfunction "VCC_47") (pintype "power_in"))
      (node (ref "U6") (pin "7") (pinfunction "VCC_7") (pintype "power_in"))
      (node (ref "U8") (pin "18") (pinfunction "VCC_18") (pintype "power_in"))
      (node (ref "U8") (pin "25") (pinfunction "VCC_25") (pintype "power_in"))
      (node (ref "U8") (pin "31") (pinfunction "VCC_31") (pintype "power_in"))
      (node (ref "U8") (pin "35") (pinfunction "VCC_35") (pintype "power_in"))
      (node (ref "U8") (pin "38") (pinfunction "VCC_38") (pintype "power_in"))
      (node (ref "U8") (pin "42") (pinfunction "VCC_42") (pintype "power_in"))
      (node (ref "U8") (pin "47") (pinfunction "VCC_47") (pintype "power_in"))
      (node (ref "U8") (pin "7") (pinfunction "VCC_7") (pintype "power_in"))
    )
    (net (code "5") (name "/FV_A1") (class "Default")
      (node (ref "U6") (pin "23") (pinfunction "3A8_23") (pintype "bidirectional"))
    )
    (net (code "6") (name "/FV_A2") (class "Default")
      (node (ref "U6") (pin "20") (pinfunction "3A6_20") (pintype "bidirectional"))
    )
    (net (code "7") (name "/FV_A3") (class "Default")
      (node (ref "U6") (pin "16") (pinfunction "3A4_16") (pintype "bidirectional"))
    )
    (net (code "8") (name "/FV_A4") (class "Default")
      (node (ref "U6") (pin "12") (pinfunction "3A2_12") (pintype "bidirectional"))
    )
    (net (code "9") (name "/FV_A5") (class "Default")
      (node (ref "U5") (pin "23") (pinfunction "3A8_23") (pintype "bidirectional"))
    )
    (net (code "10") (name "/FV_A6") (class "Default")
      (node (ref "U5") (pin "20") (pinfunction "3A6_20") (pintype "bidirectional"))
    )
    (net (code "11") (name "/FV_A7") (class "Default")
      (node (ref "U5") (pin "16") (pinfunction "3A4_16") (pintype "bidirectional"))
    )
    (net (code "12") (name "/FV_A8") (class "Default")
      (node (ref "U6") (pin "22") (pinfunction "3A7_22") (pintype "bidirectional"))
    )
    (net (code "13") (name "/FV_A9") (class "Default")
      (node (ref "U6") (pin "19") (pinfunction "3A5_19") (pintype "bidirectional"))
    )
    (net (code "14") (name "/FV_A10") (class "Default")
      (node (ref "U6") (pin "13") (pinfunction "3A3_13") (pintype "bidirectional"))
    )
    (net (code "15") (name "/FV_A11") (class "Default")
      (node (ref "U6") (pin "9") (pinfunction "3A1_9") (pintype "bidirectional"))
    )
    (net (code "16") (name "/FV_A12") (class "Default")
      (node (ref "U5") (pin "22") (pinfunction "3A7_22") (pintype "bidirectional"))
    )
    (net (code "17") (name "/FV_A13") (class "Default")
      (node (ref "U5") (pin "19") (pinfunction "3A5_19") (pintype "bidirectional"))
    )
    (net (code "18") (name "/FV_A14") (class "Default")
      (node (ref "U5") (pin "13") (pinfunction "3A3_13") (pintype "bidirectional"))
    )
    (net (code "19") (name "/FV_A15") (class "Default")
      (node (ref "U5") (pin "12") (pinfunction "3A2_12") (pintype "bidirectional"))
    )
    (net (code "20") (name "/FV_A16") (class "Default")
      (node (ref "U5") (pin "9") (pinfunction "3A1_9") (pintype "bidirectional"))
    )
    (net (code "21") (name "/FV_A17") (class "Default")
      (node (ref "U4") (pin "23") (pinfunction "3A8_23") (pintype "bidirectional"))
    )
    (net (code "22") (name "/FV_A18") (class "Default")
      (node (ref "U4") (pin "22") (pinfunction "3A7_22") (pintype "bidirectional"))
    )
    (net (code "23") (name "/FV_A19") (class "Default")
      (node (ref "U4") (pin "20") (pinfunction "3A6_20") (pintype "bidirectional"))
    )
    (net (code "24") (name "/FV_A20") (class "Default")
      (node (ref "U4") (pin "19") (pinfunction "3A5_19") (pintype "bidirectional"))
    )
    (net (code "25") (name "/FV_A21") (class "Default")
      (node (ref "U4") (pin "16") (pinfunction "3A4_16") (pintype "bidirectional"))
    )
    (net (code "26") (name "/FV_A22") (class "Default")
      (node (ref "U4") (pin "13") (pinfunction "3A3_13") (pintype "bidirectional"))
    )
    (net (code "27") (name "/FV_A23") (class "Default")
      (node (ref "U4") (pin "12") (pinfunction "3A2_12") (pintype "bidirectional"))
    )
    (net (code "28") (name "/FV_A24") (class "Default")
      (node (ref "U8") (pin "9") (pinfunction "3A1_9") (pintype "bidirectional"))
    )
    (net (code "29") (name "/FV_A25") (class "Default")
      (node (ref "U8") (pin "12") (pinfunction "3A2_12") (pintype "bidirectional"))
    )
    (net (code "30") (name "/FV_A26") (class "Default")
      (node (ref "U8") (pin "13") (pinfunction "3A3_13") (pintype "bidirectional"))
    )
    (net (code "31") (name "/FV_A27") (class "Default")
      (node (ref "U8") (pin "16") (pinfunction "3A4_16") (pintype "bidirectional"))
    )
    (net (code "32") (name "/FV_A28") (class "Default")
      (node (ref "U8") (pin "19") (pinfunction "3A5_19") (pintype "bidirectional"))
    )
    (net (code "33") (name "/FV_A29") (class "Default")
      (node (ref "U8") (pin "20") (pinfunction "3A6_20") (pintype "bidirectional"))
    )
    (net (code "34") (name "/FV_A30") (class "Default")
      (node (ref "U8") (pin "22") (pinfunction "3A7_22") (pintype "bidirectional"))
    )
    (net (code "35") (name "/FV_A31") (class "Default")
      (node (ref "U8") (pin "23") (pinfunction "3A8_23") (pintype "bidirectional"))
    )
    (net (code "36") (name "/FV_AD_CLKI") (class "Default")
      (node (ref "U1") (pin "17") (pinfunction "CLKBA_17") (pintype "input"))
      (node (ref "U11") (pin "17") (pinfunction "CLKBA_17") (pintype "input"))
      (node (ref "U12") (pin "17") (pinfunction "CLKBA_17") (pintype "input"))
      (node (ref "U2") (pin "17") (pinfunction "CLKBA_17") (pintype "input"))
      (node (ref "U3") (pin "17") (pinfunction "CLKBA_17") (pintype "input"))
      (node (ref "U4") (pin "17") (pinfunction "CLKBA_17") (pintype "input"))
      (node (ref "U5") (pin "17") (pinfunction "CLKBA_17") (pintype "input"))
      (node (ref "U6") (pin "17") (pinfunction "CLKBA_17") (pintype "input"))
      (node (ref "U8") (pin "17") (pinfunction "CLKBA_17") (pintype "input"))
    )
    (net (code "37") (name "/FV_AD_CLKO") (class "Default")
      (node (ref "U1") (pin "32") (pinfunction "CLKAB_32") (pintype "input"))
      (node (ref "U11") (pin "32") (pinfunction "CLKAB_32") (pintype "input"))
      (node (ref "U12") (pin "32") (pinfunction "CLKAB_32") (pintype "input"))
      (node (ref "U2") (pin "32") (pinfunction "CLKAB_32") (pintype "input"))
      (node (ref "U3") (pin "32") (pinfunction "CLKAB_32") (pintype "input"))
      (node (ref "U4") (pin "32") (pinfunction "CLKAB_32") (pintype "input"))
      (node (ref "U5") (pin "32") (pinfunction "CLKAB_32") (pintype "input"))
      (node (ref "U6") (pin "32") (pinfunction "CLKAB_32") (pintype "input"))
      (node (ref "U8") (pin "32") (pinfunction "CLKAB_32") (pintype "input"))
    )
    (net (code "38") (name "/FV_AD_LE") (class "Default")
      (node (ref "R40") (pin "2") (pintype "passive"))
      (node (ref "U1") (pin "11") (pinfunction "LE_11") (pintype "input"))
      (node (ref "U11") (pin "11") (pinfunction "LE_11") (pintype "input"))
      (node (ref "U12") (pin "11") (pinfunction "LE_11") (pintype "input"))
      (node (ref "U2") (pin "11") (pinfunction "LE_11") (pintype "input"))
      (node (ref "U4") (pin "11") (pinfunction "LE_11") (pintype "input"))
      (node (ref "U5") (pin "11") (pinfunction "LE_11") (pintype "input"))
      (node (ref "U6") (pin "11") (pinfunction "LE_11") (pintype "input"))
      (node (ref "U8") (pin "11") (pinfunction "LE_11") (pintype "input"))
    )
    (net (code "39") (name "/FV_AD_~{OE}") (class "Default")
      (node (ref "R9") (pin "2") (pintype "passive"))
      (node (ref "U1") (pin "14") (pinfunction "~{OE}_14") (pintype "input"))
      (node (ref "U11") (pin "14") (pinfunction "~{OE}_14") (pintype "input"))
      (node (ref "U12") (pin "14") (pinfunction "~{OE}_14") (pintype "input"))
      (node (ref "U2") (pin "14") (pinfunction "~{OE}_14") (pintype "input"))
      (node (ref "U3") (pin "14") (pinfunction "~{OE}_14") (pintype "input"))
      (node (ref "U4") (pin "14") (pinfunction "~{OE}_14") (pintype "input"))
      (node (ref "U5") (pin "14") (pinfunction "~{OE}_14") (pintype "input"))
      (node (ref "U6") (pin "14") (pinfunction "~{OE}_14") (pintype "input"))
      (node (ref "U8") (pin "14") (pinfunction "~{OE}_14") (pintype "input"))
    )
    (net (code "40") (name "/FV_AM0") (class "Default")
      (node (ref "U3") (pin "13") (pinfunction "3A3_13") (pintype "bidirectional"))
    )
    (net (code "41") (name "/FV_AM1") (class "Default")
      (node (ref "U3") (pin "16") (pinfunction "3A4_16") (pintype "bidirectional"))
    )
    (net (code "42") (name "/FV_AM2") (class "Default")
      (node (ref "U3") (pin "19") (pinfunction "3A5_19") (pintype "bidirectional"))
    )
    (net (code "43") (name "/FV_AM3") (class "Default")
      (node (ref "U3") (pin "20") (pinfunction "3A6_20") (pintype "bidirectional"))
    )
    (net (code "44") (name "/FV_AM4") (class "Default")
      (node (ref "U3") (pin "23") (pinfunction "3A8_23") (pintype "bidirectional"))
    )
    (net (code "45") (name "/FV_AM5") (class "Default")
      (node (ref "U3") (pin "12") (pinfunction "3A2_12") (pintype "bidirectional"))
    )
    (net (code "48") (name "/FV_A_DIR") (class "Default")
      (node (ref "R44") (pin "2") (pintype "passive"))
      (node (ref "U4") (pin "24") (pinfunction "DIR_24") (pintype "input"))
      (node (ref "U5") (pin "24") (pinfunction "DIR_24") (pintype "input"))
      (node (ref "U6") (pin "24") (pinfunction "DIR_24") (pintype "input"))
      (node (ref "U8") (pin "24") (pinfunction "DIR_24") (pintype "input"))
    )
    (net (code "50") (name "/FV_D0") (class "Default")
      (node (ref "U1") (pin "9") (pinfunction "3A1_9") (pintype "bidirectional"))
    )
    (net (code "51") (name "/FV_D1") (class "Default")
      (node (ref "U1") (pin "13") (pinfunction "3A3_13") (pintype "bidirectional"))
    )
    (net (code "52") (name "/FV_D2") (class "Default")
      (node (ref "U1") (pin "19") (pinfunction "3A5_19") (pintype "bidirectional"))
    )
    (net (code "53") (name "/FV_D3") (class "Default")
      (node (ref "U1") (pin "22") (pinfunction "3A7_22") (pintype "bidirectional"))
    )
    (net (code "54") (name "/FV_D4") (class "Default")
      (node (ref "U2") (pin "9") (pinfunction "3A1_9") (pintype "bidirectional"))
    )
    (net (code "55") (name "/FV_D5") (class "Default")
      (node (ref "U2") (pin "13") (pinfunction "3A3_13") (pintype "bidirectional"))
    )
    (net (code "56") (name "/FV_D6") (class "Default")
      (node (ref "U2") (pin "19") (pinfunction "3A5_19") (pintype "bidirectional"))
    )
    (net (code "57") (name "/FV_D7") (class "Default")
      (node (ref "U2") (pin "22") (pinfunction "3A7_22") (pintype "bidirectional"))
    )
    (net (code "58") (name "/FV_D8") (class "Default")
      (node (ref "U1") (pin "12") (pinfunction "3A2_12") (pintype "bidirectional"))
    )
    (net (code "59") (name "/FV_D9") (class "Default")
      (node (ref "U1") (pin "16") (pinfunction "3A4_16") (pintype "bidirectional"))
    )
    (net (code "60") (name "/FV_D10") (class "Default")
      (node (ref "U1") (pin "20") (pinfunction "3A6_20") (pintype "bidirectional"))
    )
    (net (code "61") (name "/FV_D11") (class "Default")
      (node (ref "U1") (pin "23") (pinfunction "3A8_23") (pintype "bidirectional"))
    )
    (net (code "62") (name "/FV_D12") (class "Default")
      (node (ref "U2") (pin "12") (pinfunction "3A2_12") (pintype "bidirectional"))
    )
    (net (code "63") (name "/FV_D13") (class "Default")
      (node (ref "U2") (pin "16") (pinfunction "3A4_16") (pintype "bidirectional"))
    )
    (net (code "64") (name "/FV_D14") (class "Default")
      (node (ref "U2") (pin "20") (pinfunction "3A6_20") (pintype "bidirectional"))
    )
    (net (code "65") (name "/FV_D15") (class "Default")
      (node (ref "U2") (pin "23") (pinfunction "3A8_23") (pintype "bidirectional"))
    )
    (net (code "66") (name "/FV_D16") (class "Default")
      (node (ref "U11") (pin "9") (pinfunction "3A1_9") (pintype "bidirectional"))
    )
    (net (code "67") (name "/FV_D17") (class "Default")
      (node (ref "U11") (pin "12") (pinfunction "3A2_12") (pintype "bidirectional"))
    )
    (net (code "68") (name "/FV_D18") (class "Default")
      (node (ref "U11") (pin "13") (pinfunction "3A3_13") (pintype "bidirectional"))
    )
    (net (code "69") (name "/FV_D19") (class "Default")
      (node (ref "U11") (pin "16") (pinfunction "3A4_16") (pintype "bidirectional"))
    )
    (net (code "70") (name "/FV_D20") (class "Default")
      (node (ref "U11") (pin "19") (pinfunction "3A5_19") (pintype "bidirectional"))
    )
    (net (code "71") (name "/FV_D21") (class "Default")
      (node (ref "U11") (pin "20") (pinfunction "3A6_20") (pintype "bidirectional"))
    )
    (net (code "72") (name "/FV_D22") (class "Default")
      (node (ref "U11") (pin "22") (pinfunction "3A7_22") (pintype "bidirectional"))
    )
    (net (code "73") (name "/FV_D23") (class "Default")
      (node (ref "U11") (pin "23") (pinfunction "3A8_23") (pintype "bidirectional"))
    )
    (net (code "74") (name "/FV_D24") (class "Default")
      (node (ref "U12") (pin "9") (pinfunction "3A1_9") (pintype "bidirectional"))
    )
    (net (code "75") (name "/FV_D25") (class "Default")
      (node (ref "U12") (pin "12") (pinfunction "3A2_12") (pintype "bidirectional"))
    )
    (net (code "76") (name "/FV_D26") (class "Default")
      (node (ref "U12") (pin "13") (pinfunction "3A3_13") (pintype "bidirectional"))
    )
    (net (code "77") (name "/FV_D27") (class "Default")
      (node (ref "U12") (pin "16") (pinfunction "3A4_16") (pintype "bidirectional"))
    )
    (net (code "78") (name "/FV_D28") (class "Default")
      (node (ref "U12") (pin "19") (pinfunction "3A5_19") (pintype "bidirectional"))
    )
    (net (code "79") (name "/FV_D29") (class "Default")
      (node (ref "U12") (pin "20") (pinfunction "3A6_20") (pintype "bidirectional"))
    )
    (net (code "80") (name "/FV_D30") (class "Default")
      (node (ref "U12") (pin "22") (pinfunction "3A7_22") (pintype "bidirectional"))
    )
    (net (code "81") (name "/FV_D31") (class "Default")
      (node (ref "U12") (pin "23") (pinfunction "3A8_23") (pintype "bidirectional"))
    )
    (net (code "82") (name "/FV_DB_DIR") (class "Default")
      (node (ref "R1") (pin "1") (pintype "passive"))
      (node (ref "U3") (pin "24") (pinfunction "DIR_24") (pintype "input"))
    )
    (net (code "83") (name "/FV_DB_LE") (class "Default")
      (node (ref "R4") (pin "2") (pintype "passive"))
      (node (ref "U3") (pin "11") (pinfunction "LE_11") (pintype "input"))
    )
    (net (code "85") (name "/FV_D_DIR") (class "Default")
      (node (ref "R39") (pin "2") (pintype "passive"))
      (node (ref "U1") (pin "24") (pinfunction "DIR_24") (pintype "input"))
      (node (ref "U11") (pin "24") (pinfunction "DIR_24") (pintype "input"))
      (node (ref "U12") (pin "24") (pinfunction "DIR_24") (pintype "input"))
      (node (ref "U2") (pin "24") (pinfunction "DIR_24") (pintype "input"))
    )
    (net (code "86") (name "/FV_I_SYSCLK") (class "Default")
      (node (ref "U1") (pin "6") (pinfunction "2Y_6") (pintype "tri_state"))
    )
    (net (code "87") (name "/FV_I_~{ACFAIL}") (class "Default")
      (node (ref "U1") (pin "3") (pinfunction "1Y_3") (pintype "tri_state"))
    )
    (net (code "88") (name "/FV_I_~{AS}") (class "Default")
      (node (ref "U4") (pin "6") (pinfunction "2Y_6") (pintype "tri_state"))
    )
    (net (code "89") (name "/FV_I_~{BERR}") (class "Default")
      (node (ref "U14") (pin "3") (pinfunction "1Y_3") (pintype "tri_state"))
    )
    (net (code "90") (name "/FV_I_~{DS}0") (class "Default")
      (node (ref "U3") (pin "6") (pinfunction "2Y_6") (pintype "tri_state"))
    )
    (net (code "91") (name "/FV_I_~{DS}1") (class "Default")
      (node (ref "U3") (pin "3") (pinfunction "1Y_3") (pintype "tri_state"))
    )
    (net (code "92") (name "/FV_I_~{DTACK}") (class "Default")
      (node (ref "U4") (pin "3") (pinfunction "1Y_3") (pintype "tri_state"))
    )
    (net (code "93") (name "/FV_I_~{IRQ}1") (class "Default")
      (node (ref "U12") (pin "6") (pinfunction "2Y_6") (pintype "tri_state"))
    )
    (net (code "94") (name "/FV_I_~{IRQ}2") (class "Default")
      (node (ref "U12") (pin "3") (pinfunction "1Y_3") (pintype "tri_state"))
    )
    (net (code "95") (name "/FV_I_~{IRQ}3") (class "Default")
      (node (ref "U11") (pin "6") (pinfunction "2Y_6") (pintype "tri_state"))
    )
    (net (code "96") (name "/FV_I_~{IRQ}4") (class "Default")
      (node (ref "U11") (pin "3") (pinfunction "1Y_3") (pintype "tri_state"))
    )
    (net (code "97") (name "/FV_I_~{IRQ}5") (class "Default")
      (node (ref "U8") (pin "6") (pinfunction "2Y_6") (pintype "tri_state"))
    )
    (net (code "98") (name "/FV_I_~{IRQ}6") (class "Default")
      (node (ref "U6") (pin "6") (pinfunction "2Y_6") (pintype "tri_state"))
    )
    (net (code "99") (name "/FV_I_~{IRQ}7") (class "Default")
      (node (ref "U6") (pin "3") (pinfunction "1Y_3") (pintype "tri_state"))
    )
    (net (code "101") (name "/FV_I_~{RESP}") (class "Default")
      (node (ref "U2") (pin "6") (pinfunction "2Y_6") (pintype "tri_state"))
    )
    (net (code "102") (name "/FV_I_~{RETRY}") (class "Default")
      (node (ref "U8") (pin "3") (pinfunction "1Y_3") (pintype "tri_state"))
    )
    (net (code "103") (name "/FV_I_~{SYSFAIL}") (class "Default")
      (node (ref "U2") (pin "3") (pinfunction "1Y_3") (pintype "tri_state"))
    )
    (net (code "104") (name "/FV_I_~{SYSRESET}") (class "Default")
      (node (ref "U14") (pin "6") (pinfunction "2Y_6") (pintype "tri_state"))
    )
    (net (code "105") (name "/FV_OE_SYSCLK") (class "Default")
      (node (ref "R19") (pin "2") (pintype "passive"))
      (node (ref "U1") (pin "41") (pinfunction "2OEAB_41") (pintype "input"))
    )
    (net (code "106") (name "/FV_OE_~{ACFAIL}") (class "Default")
      (node (ref "R28") (pin "2") (pintype "passive"))
      (node (ref "U1") (pin "48") (pinfunction "1OEAB_48") (pintype "input"))
    )
    (net (code "107") (name "/FV_OE_~{BERR}") (class "Default")
      (node (ref "R27") (pin "2") (pintype "passive"))
      (node (ref "U14") (pin "48") (pinfunction "1OEAB_48") (pintype "input"))
    )
    (net (code "108") (name "/FV_OE_~{DAS}") (class "Default")
      (node (ref "R38") (pin "2") (pintype "passive"))
      (node (ref "U3") (pin "41") (pinfunction "2OEAB_41") (pintype "input"))
      (node (ref "U3") (pin "48") (pinfunction "1OEAB_48") (pintype "input"))
      (node (ref "U4") (pin "41") (pinfunction "2OEAB_41") (pintype "input"))
    )
    (net (code "109") (name "/FV_OE_~{DTACK}") (class "Default")
      (node (ref "R31") (pin "2") (pintype "passive"))
      (node (ref "U4") (pin "48") (pinfunction "1OEAB_48") (pintype "input"))
    )
    (net (code "110") (name "/FV_OE_~{IRQ}1") (class "Default")
      (node (ref "R6") (pin "2") (pintype "passive"))
      (node (ref "U12") (pin "41") (pinfunction "2OEAB_41") (pintype "input"))
    )
    (net (code "111") (name "/FV_OE_~{IRQ}2") (class "Default")
      (node (ref "R8") (pin "2") (pintype "passive"))
      (node (ref "U12") (pin "48") (pinfunction "1OEAB_48") (pintype "input"))
    )
    (net (code "112") (name "/FV_OE_~{IRQ}3") (class "Default")
      (node (ref "R10") (pin "2") (pintype "passive"))
      (node (ref "U11") (pin "41") (pinfunction "2OEAB_41") (pintype "input"))
    )
    (net (code "113") (name "/FV_OE_~{IRQ}4") (class "Default")
      (node (ref "R12") (pin "2") (pintype "passive"))
      (node (ref "U11") (pin "48") (pinfunction "1OEAB_48") (pintype "input"))
    )
    (net (code "114") (name "/FV_OE_~{IRQ}5") (class "Default")
      (node (ref "R13") (pin "2") (pintype "passive"))
      (node (ref "U8") (pin "41") (pinfunction "2OEAB_41") (pintype "input"))
    )
    (net (code "115") (name "/FV_OE_~{IRQ}6") (class "Default")
      (node (ref "R15") (pin "2") (pintype "passive"))
      (node (ref "U6") (pin "41") (pinfunction "2OEAB_41") (pintype "input"))
    )
    (net (code "116") (name "/FV_OE_~{IRQ}7") (class "Default")
      (node (ref "R18") (pin "2") (pintype "passive"))
      (node (ref "U6") (pin "48") (pinfunction "1OEAB_48") (pintype "input"))
    )
    (net (code "117") (name "/FV_OE_~{RESP}") (class "Default")
      (node (ref "R30") (pin "2") (pintype "passive"))
      (node (ref "U2") (pin "41") (pinfunction "2OEAB_41") (pintype "input"))
    )
    (net (code "118") (name "/FV_OE_~{RETRY}") (class "Default")
      (node (ref "R25") (pin "2") (pintype "passive"))
      (node (ref "U8") (pin "48") (pinfunction "1OEAB_48") (pintype "input"))
    )
    (net (code "119") (name "/FV_OE_~{SYSFAIL}") (class "Default")
      (node (ref "R37") (pin "2") (pintype "passive"))
      (node (ref "U2") (pin "48") (pinfunction "1OEAB_48") (pintype "input"))
    )
    (net (code "120") (name "/FV_OE_~{SYSRESET}") (class "Default")
      (node (ref "R54") (pin "2") (pintype "passive"))
      (node (ref "U14") (pin "41") (pinfunction "2OEAB_41") (pintype "input"))
    )
    (net (code "121") (name "/FV_O_SYSCLK") (class "Default")
      (node (ref "U1") (pin "5") (pinfunction "2A_5") (pintype "input"))
    )
    (net (code "122") (name "/FV_O_~{AS}") (class "Default")
      (node (ref "U4") (pin "5") (pinfunction "2A_5") (pintype "input"))
    )
    (net (code "123") (name "/FV_O_~{DS}0") (class "Default")
      (node (ref "U3") (pin "5") (pinfunction "2A_5") (pintype "input"))
    )
    (net (code "124") (name "/FV_O_~{DS}1") (class "Default")
      (node (ref "U3") (pin "2") (pinfunction "1A_2") (pintype "input"))
    )
    (net (code "125") (name "/FV_O_~{DTACK}") (class "Default")
      (node (ref "U4") (pin "2") (pinfunction "1A_2") (pintype "input"))
    )
    (net (code "126") (name "/FV_O_~{RESP}") (class "Default")
      (node (ref "U2") (pin "5") (pinfunction "2A_5") (pintype "input"))
    )
    (net (code "127") (name "/FV_O_~{RETRY}") (class "Default")
      (node (ref "U8") (pin "2") (pinfunction "1A_2") (pintype "input"))
    )
    (net (code "128") (name "/FV_~{GA}0") (class "Default")
      (node (ref "U14") (pin "12") (pinfunction "3A2_12") (pintype "bidirectional"))
    )
    (net (code "129") (name "/FV_~{GA}1") (class "Default")
      (node (ref "U14") (pin "13") (pinfunction "3A3_13") (pintype "bidirectional"))
    )
    (net (code "130") (name "/FV_~{GA}2") (class "Default")
      (node (ref "U14") (pin "16") (pinfunction "3A4_16") (pintype "bidirectional"))
    )
    (net (code "131") (name "/FV_~{GA}3") (class "Default")
      (node (ref "U14") (pin "19") (pinfunction "3A5_19") (pintype "bidirectional"))
    )
    (net (code "132") (name "/FV_~{GA}4") (class "Default")
      (node (ref "U14") (pin "20") (pinfunction "3A6_20") (pintype "bidirectional"))
    )
    (net (code "133") (name "/FV_~{GA}5") (class "Default")
      (node (ref "U14") (pin "9") (pinfunction "3A1_9") (pintype "bidirectional"))
    )
    (net (code "135") (name "/FV_~{IACKIN}") (class "Default")
      (node (ref "U5") (pin "3") (pinfunction "1Y_3") (pintype "tri_state"))
    )
    (net (code "136") (name "/FV_~{IACKOUT}") (class "Default")
      (node (ref "U5") (pin "5") (pinfunction "2A_5") (pintype "input"))
    )
    (net (code "137") (name "/FV_~{IACK}") (class "Default")
      (node (ref "U3") (pin "22") (pinfunction "3A7_22") (pintype "bidirectional"))
    )
    (net (code "138") (name "/FV_~{IE}_DBRQ") (class "Default")
      (node (ref "U14") (pin "1") (pinfunction "1~{OEBY}_1") (pintype "input"))
      (node (ref "U2") (pin "8") (pinfunction "2~{OEBY}_8") (pintype "input"))
      (node (ref "U4") (pin "1") (pinfunction "1~{OEBY}_1") (pintype "input"))
      (node (ref "U8") (pin "1") (pinfunction "1~{OEBY}_1") (pintype "input"))
    )
    (net (code "139") (name "/FV_~{IE}_SYSCLK") (class "Default")
      (node (ref "U1") (pin "8") (pinfunction "2~{OEBY}_8") (pintype "input"))
    )
    (net (code "140") (name "/FV_~{IE}_~{ACFAIL}") (class "Default")
      (node (ref "U1") (pin "1") (pinfunction "1~{OEBY}_1") (pintype "input"))
    )
    (net (code "141") (name "/FV_~{IE}_~{DAS}") (class "Default")
      (node (ref "R2") (pin "2") (pintype "passive"))
      (node (ref "U3") (pin "1") (pinfunction "1~{OEBY}_1") (pintype "input"))
      (node (ref "U3") (pin "8") (pinfunction "2~{OEBY}_8") (pintype "input"))
      (node (ref "U4") (pin "8") (pinfunction "2~{OEBY}_8") (pintype "input"))
    )
    (net (code "142") (name "/FV_~{IE}_~{IRQ}") (class "Default")
      (node (ref "U11") (pin "1") (pinfunction "1~{OEBY}_1") (pintype "input"))
      (node (ref "U11") (pin "8") (pinfunction "2~{OEBY}_8") (pintype "input"))
      (node (ref "U12") (pin "1") (pinfunction "1~{OEBY}_1") (pintype "input"))
      (node (ref "U12") (pin "8") (pinfunction "2~{OEBY}_8") (pintype "input"))
      (node (ref "U6") (pin "1") (pinfunction "1~{OEBY}_1") (pintype "input"))
      (node (ref "U6") (pin "8") (pinfunction "2~{OEBY}_8") (pintype "input"))
      (node (ref "U8") (pin "8") (pinfunction "2~{OEBY}_8") (pintype "input"))
    )
    (net (code "143") (name "/FV_~{IE}_~{SYSFAIL}") (class "Default")
      (node (ref "U2") (pin "1") (pinfunction "1~{OEBY}_1") (pintype "input"))
    )
    (net (code "144") (name "/FV_~{IE}_~{SYSRESET}") (class "Default")
      (node (ref "R14") (pin "2") (pintype "passive"))
      (node (ref "U14") (pin "8") (pinfunction "2~{OEBY}_8") (pintype "input"))
    )
    (net (code "145") (name "/FV_~{LWORD}") (class "Default")
      (node (ref "U4") (pin "9") (pinfunction "3A1_9") (pintype "bidirectional"))
    )
    (net (code "146") (name "/FV_~{WRITE}") (class "Default")
      (node (ref "U3") (pin "9") (pinfunction "3A1_9") (pintype "bidirectional"))
    )
    (net (code "147") (name "/VME_A1") (class "Default")
      (node (ref "U6") (pin "26") (pinfunction "3B8_26") (pintype "bidirectional"))
    )
    (net (code "148") (name "/VME_A2") (class "Default")
      (node (ref "U6") (pin "29") (pinfunction "3B6_29") (pintype "bidirectional"))
    )
    (net (code "149") (name "/VME_A3") (class "Default")
      (node (ref "U6") (pin "33") (pinfunction "3B4_33") (pintype "bidirectional"))
    )
    (net (code "150") (name "/VME_A4") (class "Default")
      (node (ref "U6") (pin "37") (pinfunction "3B2_37") (pintype "bidirectional"))
    )
    (net (code "151") (name "/VME_A5") (class "Default")
      (node (ref "U5") (pin "26") (pinfunction "3B8_26") (pintype "bidirectional"))
    )
    (net (code "152") (name "/VME_A6") (class "Default")
      (node (ref "U5") (pin "29") (pinfunction "3B6_29") (pintype "bidirectional"))
    )
    (net (code "153") (name "/VME_A7") (class "Default")
      (node (ref "U5") (pin "33") (pinfunction "3B4_33") (pintype "bidirectional"))
    )
    (net (code "154") (name "/VME_A8") (class "Default")
      (node (ref "U6") (pin "27") (pinfunction "3B7_27") (pintype "bidirectional"))
    )
    (net (code "155") (name "/VME_A9") (class "Default")
      (node (ref "U6") (pin "30") (pinfunction "3B5_30") (pintype "bidirectional"))
    )
    (net (code "156") (name "/VME_A10") (class "Default")
      (node (ref "U6") (pin "36") (pinfunction "3B3_36") (pintype "bidirectional"))
    )
    (net (code "157") (name "/VME_A11") (class "Default")
      (node (ref "U6") (pin "40") (pinfunction "3B1_40") (pintype "bidirectional"))
    )
    (net (code "158") (name "/VME_A12") (class "Default")
      (node (ref "U5") (pin "27") (pinfunction "3B7_27") (pintype "bidirectional"))
    )
    (net (code "159") (name "/VME_A13") (class "Default")
      (node (ref "U5") (pin "30") (pinfunction "3B5_30") (pintype "bidirectional"))
    )
    (net (code "160") (name "/VME_A14") (class "Default")
      (node (ref "U5") (pin "36") (pinfunction "3B3_36") (pintype "bidirectional"))
    )
    (net (code "161") (name "/VME_A15") (class "Default")
      (node (ref "U5") (pin "37") (pinfunction "3B2_37") (pintype "bidirectional"))
    )
    (net (code "162") (name "/VME_A16") (class "Default")
      (node (ref "U5") (pin "40") (pinfunction "3B1_40") (pintype "bidirectional"))
    )
    (net (code "163") (name "/VME_A17") (class "Default")
      (node (ref "U4") (pin "26") (pinfunction "3B8_26") (pintype "bidirectional"))
    )
    (net (code "164") (name "/VME_A18") (class "Default")
      (node (ref "U4") (pin "27") (pinfunction "3B7_27") (pintype "bidirectional"))
    )
    (net (code "165") (name "/VME_A19") (class "Default")
      (node (ref "U4") (pin "29") (pinfunction "3B6_29") (pintype "bidirectional"))
    )
    (net (code "166") (name "/VME_A20") (class "Default")
      (node (ref "U4") (pin "30") (pinfunction "3B5_30") (pintype "bidirectional"))
    )
    (net (code "167") (name "/VME_A21") (class "Default")
      (node (ref "U4") (pin "33") (pinfunction "3B4_33") (pintype "bidirectional"))
    )
    (net (code "168") (name "/VME_A22") (class "Default")
      (node (ref "U4") (pin "36") (pinfunction "3B3_36") (pintype "bidirectional"))
    )
    (net (code "169") (name "/VME_A23") (class "Default")
      (node (ref "U4") (pin "37") (pinfunction "3B2_37") (pintype "bidirectional"))
    )
    (net (code "170") (name "/VME_A24") (class "Default")
      (node (ref "U8") (pin "40") (pinfunction "3B1_40") (pintype "bidirectional"))
    )
    (net (code "171") (name "/VME_A25") (class "Default")
      (node (ref "U8") (pin "37") (pinfunction "3B2_37") (pintype "bidirectional"))
    )
    (net (code "172") (name "/VME_A26") (class "Default")
      (node (ref "U8") (pin "36") (pinfunction "3B3_36") (pintype "bidirectional"))
    )
    (net (code "173") (name "/VME_A27") (class "Default")
      (node (ref "U8") (pin "33") (pinfunction "3B4_33") (pintype "bidirectional"))
    )
    (net (code "174") (name "/VME_A28") (class "Default")
      (node (ref "U8") (pin "30") (pinfunction "3B5_30") (pintype "bidirectional"))
    )
    (net (code "175") (name "/VME_A29") (class "Default")
      (node (ref "U8") (pin "29") (pinfunction "3B6_29") (pintype "bidirectional"))
    )
    (net (code "176") (name "/VME_A30") (class "Default")
      (node (ref "U8") (pin "27") (pinfunction "3B7_27") (pintype "bidirectional"))
    )
    (net (code "177") (name "/VME_A31") (class "Default")
      (node (ref "U8") (pin "26") (pinfunction "3B8_26") (pintype "bidirectional"))
    )
    (net (code "178") (name "/VME_AM0") (class "Default")
      (node (ref "U3") (pin "36") (pinfunction "3B3_36") (pintype "bidirectional"))
    )
    (net (code "179") (name "/VME_AM1") (class "Default")
      (node (ref "U3") (pin "33") (pinfunction "3B4_33") (pintype "bidirectional"))
    )
    (net (code "180") (name "/VME_AM2") (class "Default")
      (node (ref "U3") (pin "30") (pinfunction "3B5_30") (pintype "bidirectional"))
    )
    (net (code "181") (name "/VME_AM3") (class "Default")
      (node (ref "U3") (pin "29") (pinfunction "3B6_29") (pintype "bidirectional"))
    )
    (net (code "182") (name "/VME_AM4") (class "Default")
      (node (ref "U3") (pin "26") (pinfunction "3B8_26") (pintype "bidirectional"))
    )
    (net (code "183") (name "/VME_AM5") (class "Default")
      (node (ref "U3") (pin "37") (pinfunction "3B2_37") (pintype "bidirectional"))
    )
    (net (code "187") (name "/VME_D0") (class "Default")
      (node (ref "U1") (pin "40") (pinfunction "3B1_40") (pintype "bidirectional"))
    )
    (net (code "188") (name "/VME_D1") (class "Default")
      (node (ref "U1") (pin "36") (pinfunction "3B3_36") (pintype "bidirectional"))
    )
    (net (code "189") (name "/VME_D2") (class "Default")
      (node (ref "U1") (pin "30") (pinfunction "3B5_30") (pintype "bidirectional"))
    )
    (net (code "190") (name "/VME_D3") (class "Default")
      (node (ref "U1") (pin "27") (pinfunction "3B7_27") (pintype "bidirectional"))
    )
    (net (code "191") (name "/VME_D4") (class "Default")
      (node (ref "U2") (pin "40") (pinfunction "3B1_40") (pintype "bidirectional"))
    )
    (net (code "192") (name "/VME_D5") (class "Default")
      (node (ref "U2") (pin "36") (pinfunction "3B3_36") (pintype "bidirectional"))
    )
    (net (code "193") (name "/VME_D6") (class "Default")
      (node (ref "U2") (pin "30") (pinfunction "3B5_30") (pintype "bidirectional"))
    )
    (net (code "194") (name "/VME_D7") (class "Default")
      (node (ref "U2") (pin "27") (pinfunction "3B7_27") (pintype "bidirectional"))
    )
    (net (code "195") (name "/VME_D8") (class "Default")
      (node (ref "U1") (pin "37") (pinfunction "3B2_37") (pintype "bidirectional"))
    )
    (net (code "196") (name "/VME_D9") (class "Default")
      (node (ref "U1") (pin "33") (pinfunction "3B4_33") (pintype "bidirectional"))
    )
    (net (code "197") (name "/VME_D10") (class "Default")
      (node (ref "U1") (pin "29") (pinfunction "3B6_29") (pintype "bidirectional"))
    )
    (net (code "198") (name "/VME_D11") (class "Default")
      (node (ref "U1") (pin "26") (pinfunction "3B8_26") (pintype "bidirectional"))
    )
    (net (code "199") (name "/VME_D12") (class "Default")
      (node (ref "U2") (pin "37") (pinfunction "3B2_37") (pintype "bidirectional"))
    )
    (net (code "200") (name "/VME_D13") (class "Default")
      (node (ref "U2") (pin "33") (pinfunction "3B4_33") (pintype "bidirectional"))
    )
    (net (code "201") (name "/VME_D14") (class "Default")
      (node (ref "U2") (pin "29") (pinfunction "3B6_29") (pintype "bidirectional"))
    )
    (net (code "202") (name "/VME_D15") (class "Default")
      (node (ref "U2") (pin "26") (pinfunction "3B8_26") (pintype "bidirectional"))
    )
    (net (code "203") (name "/VME_D16") (class "Default")
      (node (ref "U11") (pin "40") (pinfunction "3B1_40") (pintype "bidirectional"))
    )
    (net (code "204") (name "/VME_D17") (class "Default")
      (node (ref "U11") (pin "37") (pinfunction "3B2_37") (pintype "bidirectional"))
    )
    (net (code "205") (name "/VME_D18") (class "Default")
      (node (ref "U11") (pin "36") (pinfunction "3B3_36") (pintype "bidirectional"))
    )
    (net (code "206") (name "/VME_D19") (class "Default")
      (node (ref "U11") (pin "33") (pinfunction "3B4_33") (pintype "bidirectional"))
    )
    (net (code "207") (name "/VME_D20") (class "Default")
      (node (ref "U11") (pin "30") (pinfunction "3B5_30") (pintype "bidirectional"))
    )
    (net (code "208") (name "/VME_D21") (class "Default")
      (node (ref "U11") (pin "29") (pinfunction "3B6_29") (pintype "bidirectional"))
    )
    (net (code "209") (name "/VME_D22") (class "Default")
      (node (ref "U11") (pin "27") (pinfunction "3B7_27") (pintype "bidirectional"))
    )
    (net (code "210") (name "/VME_D23") (class "Default")
      (node (ref "U11") (pin "26") (pinfunction "3B8_26") (pintype "bidirectional"))
    )
    (net (code "211") (name "/VME_D24") (class "Default")
      (node (ref "U12") (pin "40") (pinfunction "3B1_40") (pintype "bidirectional"))
    )
    (net (code "212") (name "/VME_D25") (class "Default")
      (node (ref "U12") (pin "37") (pinfunction "3B2_37") (pintype "bidirectional"))
    )
    (net (code "213") (name "/VME_D26") (class "Default")
      (node (ref "U12") (pin "36") (pinfunction "3B3_36") (pintype "bidirectional"))
    )
    (net (code "214") (name "/VME_D27") (class "Default")
      (node (ref "U12") (pin "33") (pinfunction "3B4_33") (pintype "bidirectional"))
    )
    (net (code "215") (name "/VME_D28") (class "Default")
      (node (ref "U12") (pin "30") (pinfunction "3B5_30") (pintype "bidirectional"))
    )
    (net (code "216") (name "/VME_D29") (class "Default")
      (node (ref "U12") (pin "29") (pinfunction "3B6_29") (pintype "bidirectional"))
    )
    (net (code "217") (name "/VME_D30") (class "Default")
      (node (ref "U12") (pin "27") (pinfunction "3B7_27") (pintype "bidirectional"))
    )
    (net (code "218") (name "/VME_D31") (class "Default")
      (node (ref "U12") (pin "26") (pinfunction "3B8_26") (pintype "bidirectional"))
    )
    (net (code "220") (name "/VME_SYSCLK") (class "Default")
      (node (ref "U1") (pin "43") (pinfunction "2B_43") (pintype "bidirectional"))
    )
    (net (code "221") (name "/VME_~{ACFAIL}") (class "Default")
      (node (ref "U1") (pin "46") (pinfunction "1B_46") (pintype "bidirectional"))
    )
    (net (code "222") (name "/VME_~{AS}") (class "Default")
      (node (ref "U4") (pin "43") (pinfunction "2B_43") (pintype "bidirectional"))
    )
    (net (code "223") (name "/VME_~{BERR}") (class "Default")
      (node (ref "U14") (pin "46") (pinfunction "1B_46") (pintype "bidirectional"))
    )
    (net (code "224") (name "/VME_~{DS}0") (class "Default")
      (node (ref "U3") (pin "43") (pinfunction "2B_43") (pintype "bidirectional"))
    )
    (net (code "225") (name "/VME_~{DS}1") (class "Default")
      (node (ref "U3") (pin "46") (pinfunction "1B_46") (pintype "bidirectional"))
    )
    (net (code "227") (name "/VME_~{DTACK}") (class "Default")
      (node (ref "U4") (pin "46") (pinfunction "1B_46") (pintype "bidirectional"))
    )
    (net (code "228") (name "/VME_~{GA}0") (class "Default")
      (node (ref "R5") (pin "6") (pinfunction "6_6") (pintype "passive"))
      (node (ref "U14") (pin "37") (pinfunction "3B2_37") (pintype "bidirectional"))
    )
    (net (code "229") (name "/VME_~{GA}1") (class "Default")
      (node (ref "R5") (pin "7") (pinfunction "7_7") (pintype "passive"))
      (node (ref "U14") (pin "36") (pinfunction "3B3_36") (pintype "bidirectional"))
    )
    (net (code "230") (name "/VME_~{GA}2") (class "Default")
      (node (ref "R5") (pin "8") (pinfunction "8_8") (pintype "passive"))
      (node (ref "U14") (pin "33") (pinfunction "3B4_33") (pintype "bidirectional"))
    )
    (net (code "231") (name "/VME_~{GA}3") (class "Default")
      (node (ref "R17") (pin "5") (pinfunction "5_5") (pintype "passive"))
      (node (ref "U14") (pin "30") (pinfunction "3B5_30") (pintype "bidirectional"))
    )
    (net (code "232") (name "/VME_~{GA}4") (class "Default")
      (node (ref "R17") (pin "6") (pinfunction "6_6") (pintype "passive"))
      (node (ref "U14") (pin "29") (pinfunction "3B6_29") (pintype "bidirectional"))
    )
    (net (code "233") (name "/VME_~{GA}5") (class "Default")
      (node (ref "R5") (pin "5") (pinfunction "5_5") (pintype "passive"))
      (node (ref "U14") (pin "40") (pinfunction "3B1_40") (pintype "bidirectional"))
    )
    (net (code "234") (name "/VME_~{IACKIN}") (class "Default")
      (node (ref "U5") (pin "46") (pinfunction "1B_46") (pintype "bidirectional"))
    )
    (net (code "235") (name "/VME_~{IACKOUT}") (class "Default")
      (node (ref "U5") (pin "43") (pinfunction "2B_43") (pintype "bidirectional"))
    )
    (net (code "236") (name "/VME_~{IACK}") (class "Default")
      (node (ref "U3") (pin "27") (pinfunction "3B7_27") (pintype "bidirectional"))
    )
    (net (code "237") (name "/VME_~{IRQ}1") (class "Default")
      (node (ref "U12") (pin "43") (pinfunction "2B_43") (pintype "bidirectional"))
    )
    (net (code "238") (name "/VME_~{IRQ}2") (class "Default")
      (node (ref "U12") (pin "46") (pinfunction "1B_46") (pintype "bidirectional"))
    )
    (net (code "239") (name "/VME_~{IRQ}3") (class "Default")
      (node (ref "U11") (pin "43") (pinfunction "2B_43") (pintype "bidirectional"))
    )
    (net (code "240") (name "/VME_~{IRQ}4") (class "Default")
      (node (ref "U11") (pin "46") (pinfunction "1B_46") (pintype "bidirectional"))
    )
    (net (code "241") (name "/VME_~{IRQ}5") (class "Default")
      (node (ref "U8") (pin "43") (pinfunction "2B_43") (pintype "bidirectional"))
    )
    (net (code "242") (name "/VME_~{IRQ}6") (class "Default")
      (node (ref "U6") (pin "43") (pinfunction "2B_43") (pintype "bidirectional"))
    )
    (net (code "243") (name "/VME_~{IRQ}7") (class "Default")
      (node (ref "U6") (pin "46") (pinfunction "1B_46") (pintype "bidirectional"))
    )
    (net (code "245") (name "/VME_~{LWORD}") (class "Default")
      (node (ref "U4") (pin "40") (pinfunction "3B1_40") (pintype "bidirectional"))
    )
    (net (code "246") (name "/VME_~{RESP}") (class "Default")
      (node (ref "U2") (pin "43") (pinfunction "2B_43") (pintype "bidirectional"))
    )
    (net (code "247") (name "/VME_~{RETRY}") (class "Default")
      (node (ref "U8") (pin "46") (pinfunction "1B_46") (pintype "bidirectional"))
    )
    (net (code "248") (name "/VME_~{SYSFAIL}") (class "Default")
      (node (ref "U2") (pin "46") (pinfunction "1B_46") (pintype "bidirectional"))
    )
    (net (code "249") (name "/VME_~{SYSRESET}") (class "Default")
      (node (ref "R41") (pin "2") (pintype "passive"))
      (node (ref "U14") (pin "43") (pinfunction "2B_43") (pintype "bidirectional"))
    )
    (net (code "250") (name "/VME_~{WRITE}") (class "Default")
      (node (ref "U3") (pin "40") (pinfunction "3B1_40") (pintype "bidirectional"))
    )
    (net (code "253") (name "GND") (class "Default")
      (node (ref "C1") (pin "1") (pintype "passive"))
      (node (ref "C10") (pin "1") (pintype "passive"))
      (node (ref "C11") (pin "1") (pintype "passive"))
      (node (ref "C12") (pin "1") (pintype "passive"))
      (node (ref "C13") (pin "1") (pintype "passive"))
      (node (ref "C14") (pin "1") (pintype "passive"))
      (node (ref "C15") (pin "1") (pintype "passive"))
      (node (ref "C16") (pin "1") (pintype "passive"))
      (node (ref "C17") (pin "1") (pintype "passive"))
      (node (ref "C18") (pin "1") (pintype "passive"))
      (node (ref "C19") (pin "1") (pintype "passive"))
      (node (ref "C2") (pin "1") (pintype "passive"))
      (node (ref "C20") (pin "1") (pintype "passive"))
      (node (ref "C21") (pin "1") (pintype "passive"))
      (node (ref "C22") (pin "1") (pintype "passive"))
      (node (ref "C23") (pin "1") (pintype "passive"))
      (node (ref "C24") (pin "1") (pintype "passive"))
      (node (ref "C25") (pin "1") (pintype "passive"))
      (node (ref "C26") (pin "1") (pintype "passive"))
      (node (ref "C27") (pin "1") (pintype "passive"))
      (node (ref "C28") (pin "1") (pintype "passive"))
      (node (ref "C29") (pin "1") (pintype "passive"))
      (node (ref "C3") (pin "1") (pintype "passive"))
      (node (ref "C30") (pin "1") (pintype "passive"))
      (node (ref "C31") (pin "1") (pintype "passive"))
      (node (ref "C32") (pin "1") (pintype "passive"))
      (node (ref "C33") (pin "1") (pintype "passive"))
      (node (ref "C34") (pin "1") (pintype "passive"))
      (node (ref "C35") (pin "1") (pintype "passive"))
      (node (ref "C36") (pin "1") (pintype "passive"))
      (node (ref "C37") (pin "1") (pintype "passive"))
      (node (ref "C38") (pin "1") (pintype "passive"))
      (node (ref "C39") (pin "1") (pintype "passive"))
      (node (ref "C4") (pin "1") (pintype "passive"))
      (node (ref "C40") (pin "1") (pintype "passive"))
      (node (ref "C41") (pin "1") (pintype "passive"))
      (node (ref "C42") (pin "1") (pintype "passive"))
      (node (ref "C43") (pin "1") (pintype "passive"))
      (node (ref "C44") (pin "1") (pintype "passive"))
      (node (ref "C45") (pin "1") (pintype "passive"))
      (node (ref "C46") (pin "1") (pintype "passive"))
      (node (ref "C47") (pin "1") (pintype "passive"))
      (node (ref "C48") (pin "1") (pintype "passive"))
      (node (ref "C49") (pin "1") (pintype "passive"))
      (node (ref "C5") (pin "1") (pintype "passive"))
      (node (ref "C50") (pin "1") (pintype "passive"))
      (node (ref "C51") (pin "1") (pintype "passive"))
      (node (ref "C52") (pin "1") (pintype "passive"))
      (node (ref "C53") (pin "1") (pintype "passive"))
      (node (ref "C54") (pin "1") (pintype "passive"))
      (node (ref "C55") (pin "1") (pintype "passive"))
      (node (ref "C56") (pin "1") (pintype "passive"))
      (node (ref "C57") (pin "1") (pintype "passive"))
      (node (ref "C58") (pin "1") (pintype "passive"))
      (node (ref "C59") (pin "1") (pintype "passive"))
      (node (ref "C6") (pin "1") (pintype "passive"))
      (node (ref "C60") (pin "1") (pintype "passive"))
      (node (ref "C61") (pin "1") (pintype "passive"))
      (node (ref "C62") (pin "1") (pintype "passive"))
      (node (ref "C63") (pin "1") (pintype "passive"))
      (node (ref "C64") (pin "1") (pintype "passive"))
      (node (ref "C65") (pin "1") (pintype "passive"))
      (node (ref "C66") (pin "1") (pintype "passive"))
      (node (ref "C67") (pin "1") (pintype "passive"))
      (node (ref "C68") (pin "1") (pintype "passive"))
      (node (ref "C69") (pin "1") (pintype "passive"))
      (node (ref "C7") (pin "1") (pintype "passive"))
      (node (ref "C70") (pin "1") (pintype "passive"))
      (node (ref "C8") (pin "1") (pintype "passive"))
      (node (ref "C9") (pin "1") (pintype "passive"))
      (node (ref "R1") (pin "2") (pintype "passive"))
      (node (ref "R10") (pin "1") (pintype "passive"))
      (node (ref "R12") (pin "1") (pintype "passive"))
      (node (ref "R13") (pin "1") (pintype "passive"))
      (node (ref "R14") (pin "1") (pintype "passive"))
      (node (ref "R15") (pin "1") (pintype "passive"))
      (node (ref "R18") (pin "1") (pintype "passive"))
      (node (ref "R19") (pin "1") (pintype "passive"))
      (node (ref "R2") (pin "1") (pintype "passive"))
      (node (ref "R25") (pin "1") (pintype "passive"))
      (node (ref "R27") (pin "1") (pintype "passive"))
      (node (ref "R28") (pin "1") (pintype "passive"))
      (node (ref "R30") (pin "1") (pintype "passive"))
      (node (ref "R31") (pin "1") (pintype "passive"))
      (node (ref "R38") (pin "1") (pintype "passive"))
      (node (ref "R39") (pin "1") (pintype "passive"))
      (node (ref "R44") (pin "1") (pintype "passive"))
      (node (ref "R54") (pin "1") (pintype "passive"))
      (node (ref "R6") (pin "1") (pintype "passive"))
      (node (ref "R8") (pin "1") (pintype "passive"))
      (node (ref "R9") (pin "1") (pintype "passive"))
      (node (ref "U1") (pin "10") (pinfunction "GND_10") (pintype "power_in"))
      (node (ref "U1") (pin "15") (pinfunction "GND_15") (pintype "power_in"))
      (node (ref "U1") (pin "2") (pinfunction "1A_2") (pintype "input"))
      (node (ref "U1") (pin "21") (pinfunction "GND_21") (pintype "power_in"))
      (node (ref "U1") (pin "28") (pinfunction "GND_28") (pintype "power_in"))
      (node (ref "U1") (pin "34") (pinfunction "GND_34") (pintype "power_in"))
      (node (ref "U1") (pin "39") (pinfunction "GND_39") (pintype "power_in"))
      (node (ref "U1") (pin "4") (pinfunction "GND_4") (pintype "power_in"))
      (node (ref "U1") (pin "45") (pinfunction "GND_45") (pintype "power_in"))
      (node (ref "U11") (pin "10") (pinfunction "GND_10") (pintype "power_in"))
      (node (ref "U11") (pin "15") (pinfunction "GND_15") (pintype "power_in"))
      (node (ref "U11") (pin "2") (pinfunction "1A_2") (pintype "input"))
      (node (ref "U11") (pin "21") (pinfunction "GND_21") (pintype "power_in"))
      (node (ref "U11") (pin "28") (pinfunction "GND_28") (pintype "power_in"))
      (node (ref "U11") (pin "34") (pinfunction "GND_34") (pintype "power_in"))
      (node (ref "U11") (pin "39") (pinfunction "GND_39") (pintype "power_in"))
      (node (ref "U11") (pin "4") (pinfunction "GND_4") (pintype "power_in"))
      (node (ref "U11") (pin "45") (pinfunction "GND_45") (pintype "power_in"))
      (node (ref "U11") (pin "5") (pinfunction "2A_5") (pintype "input"))
      (node (ref "U12") (pin "10") (pinfunction "GND_10") (pintype "power_in"))
      (node (ref "U12") (pin "15") (pinfunction "GND_15") (pintype "power_in"))
      (node (ref "U12") (pin "2") (pinfunction "1A_2") (pintype "input"))
      (node (ref "U12") (pin "21") (pinfunction "GND_21") (pintype "power_in"))
      (node (ref "U12") (pin "28") (pinfunction "GND_28") (pintype "power_in"))
      (node (ref "U12") (pin "34") (pinfunction "GND_34") (pintype "power_in"))
      (node (ref "U12") (pin "39") (pinfunction "GND_39") (pintype "power_in"))
      (node (ref "U12") (pin "4") (pinfunction "GND_4") (pintype "power_in"))
      (node (ref "U12") (pin "45") (pinfunction "GND_45") (pintype "power_in"))
      (node (ref "U12") (pin "5") (pinfunction "2A_5") (pintype "input"))
      (node (ref "U14") (pin "10") (pinfunction "GND_10") (pintype "power_in"))
      (node (ref "U14") (pin "14") (pinfunction "~{OE}_14") (pintype "input"))
      (node (ref "U14") (pin "15") (pinfunction "GND_15") (pintype "power_in"))
      (node (ref "U14") (pin "17") (pinfunction "CLKBA_17") (pintype "input"))
      (node (ref "U14") (pin "2") (pinfunction "1A_2") (pintype "input"))
      (node (ref "U14") (pin "21") (pinfunction "GND_21") (pintype "power_in"))
      (node (ref "U14") (pin "24") (pinfunction "DIR_24") (pintype "input"))
      (node (ref "U14") (pin "26") (pinfunction "3B8_26") (pintype "bidirectional"))
      (node (ref "U14") (pin "27") (pinfunction "3B7_27") (pintype "bidirectional"))
      (node (ref "U14") (pin "28") (pinfunction "GND_28") (pintype "power_in"))
      (node (ref "U14") (pin "32") (pinfunction "CLKAB_32") (pintype "input"))
      (node (ref "U14") (pin "34") (pinfunction "GND_34") (pintype "power_in"))
      (node (ref "U14") (pin "39") (pinfunction "GND_39") (pintype "power_in"))
      (node (ref "U14") (pin "4") (pinfunction "GND_4") (pintype "power_in"))
      (node (ref "U14") (pin "45") (pinfunction "GND_45") (pintype "power_in"))
      (node (ref "U14") (pin "5") (pinfunction "2A_5") (pintype "input"))
      (node (ref "U2") (pin "10") (pinfunction "GND_10") (pintype "power_in"))
      (node (ref "U2") (pin "15") (pinfunction "GND_15") (pintype "power_in"))
      (node (ref "U2") (pin "2") (pinfunction "1A_2") (pintype "input"))
      (node (ref "U2") (pin "21") (pinfunction "GND_21") (pintype "power_in"))
      (node (ref "U2") (pin "28") (pinfunction "GND_28") (pintype "power_in"))
      (node (ref "U2") (pin "34") (pinfunction "GND_34") (pintype "power_in"))
      (node (ref "U2") (pin "39") (pinfunction "GND_39") (pintype "power_in"))
      (node (ref "U2") (pin "4") (pinfunction "GND_4") (pintype "power_in"))
      (node (ref "U2") (pin "45") (pinfunction "GND_45") (pintype "power_in"))
      (node (ref "U3") (pin "10") (pinfunction "GND_10") (pintype "power_in"))
      (node (ref "U3") (pin "15") (pinfunction "GND_15") (pintype "power_in"))
      (node (ref "U3") (pin "21") (pinfunction "GND_21") (pintype "power_in"))
      (node (ref "U3") (pin "28") (pinfunction "GND_28") (pintype "power_in"))
      (node (ref "U3") (pin "34") (pinfunction "GND_34") (pintype "power_in"))
      (node (ref "U3") (pin "39") (pinfunction "GND_39") (pintype "power_in"))
      (node (ref "U3") (pin "4") (pinfunction "GND_4") (pintype "power_in"))
      (node (ref "U3") (pin "45") (pinfunction "GND_45") (pintype "power_in"))
      (node (ref "U4") (pin "10") (pinfunction "GND_10") (pintype "power_in"))
      (node (ref "U4") (pin "15") (pinfunction "GND_15") (pintype "power_in"))
      (node (ref "U4") (pin "21") (pinfunction "GND_21") (pintype "power_in"))
      (node (ref "U4") (pin "28") (pinfunction "GND_28") (pintype "power_in"))
      (node (ref "U4") (pin "34") (pinfunction "GND_34") (pintype "power_in"))
      (node (ref "U4") (pin "39") (pinfunction "GND_39") (pintype "power_in"))
      (node (ref "U4") (pin "4") (pinfunction "GND_4") (pintype "power_in"))
      (node (ref "U4") (pin "45") (pinfunction "GND_45") (pintype "power_in"))
      (node (ref "U5") (pin "1") (pinfunction "1~{OEBY}_1") (pintype "input"))
      (node (ref "U5") (pin "10") (pinfunction "GND_10") (pintype "power_in"))
      (node (ref "U5") (pin "15") (pinfunction "GND_15") (pintype "power_in"))
      (node (ref "U5") (pin "2") (pinfunction "1A_2") (pintype "input"))
      (node (ref "U5") (pin "21") (pinfunction "GND_21") (pintype "power_in"))
      (node (ref "U5") (pin "28") (pinfunction "GND_28") (pintype "power_in"))
      (node (ref "U5") (pin "34") (pinfunction "GND_34") (pintype "power_in"))
      (node (ref "U5") (pin "39") (pinfunction "GND_39") (pintype "power_in"))
      (node (ref "U5") (pin "4") (pinfunction "GND_4") (pintype "power_in"))
      (node (ref "U5") (pin "45") (pinfunction "GND_45") (pintype "power_in"))
      (node (ref "U5") (pin "48") (pinfunction "1OEAB_48") (pintype "input"))
      (node (ref "U6") (pin "10") (pinfunction "GND_10") (pintype "power_in"))
      (node (ref "U6") (pin "15") (pinfunction "GND_15") (pintype "power_in"))
      (node (ref "U6") (pin "2") (pinfunction "1A_2") (pintype "input"))
      (node (ref "U6") (pin "21") (pinfunction "GND_21") (pintype "power_in"))
      (node (ref "U6") (pin "28") (pinfunction "GND_28") (pintype "power_in"))
      (node (ref "U6") (pin "34") (pinfunction "GND_34") (pintype "power_in"))
      (node (ref "U6") (pin "39") (pinfunction "GND_39") (pintype "power_in"))
      (node (ref "U6") (pin "4") (pinfunction "GND_4") (pintype "power_in"))
      (node (ref "U6") (pin "45") (pinfunction "GND_45") (pintype "power_in"))
      (node (ref "U6") (pin "5") (pinfunction "2A_5") (pintype "input"))
      (node (ref "U8") (pin "10") (pinfunction "GND_10") (pintype "power_in"))
      (node (ref "U8") (pin "15") (pinfunction "GND_15") (pintype "power_in"))
      (node (ref "U8") (pin "21") (pinfunction "GND_21") (pintype "power_in"))
      (node (ref "U8") (pin "28") (pinfunction "GND_28") (pintype "power_in"))
      (node (ref "U8") (pin "34") (pinfunction "GND_34") (pintype "power_in"))
      (node (ref "U8") (pin "39") (pinfunction "GND_39") (pintype "power_in"))
      (node (ref "U8") (pin "4") (pinfunction "GND_4") (pintype "power_in"))
      (node (ref "U8") (pin "45") (pinfunction "GND_45") (pintype "power_in"))
      (node (ref "U8") (pin "5") (pinfunction "2A_5") (pintype "input"))
    )
    (net (code "254") (name "unconnected-(R17-Pad1)") (class "Default")
      (node (ref "R17") (pin "1") (pinfunction "1_1") (pintype "passive"))
    )
    (net (code "255") (name "unconnected-(R17-Pad2)") (class "Default")
      (node (ref "R17") (pin "2") (pinfunction "2_2") (pintype "passive"))
    )
    (net (code "256") (name "unconnected-(R17-Pad7)") (class "Default")
      (node (ref "R17") (pin "7") (pinfunction "7_7") (pintype "passive"))
    )
    (net (code "257") (name "unconnected-(R17-Pad8)") (class "Default")
      (node (ref "R17") (pin "8") (pinfunction "8_8") (pintype "passive"))
    )
    (net (code "258") (name "unconnected-(U5A-2Y-Pad6)") (class "Default")
      (node (ref "U5") (pin "6") (pinfunction "2Y_6") (pintype "tri_state"))
    )
    (net (code "259") (name "unconnected-(U14B-3A7-Pad22)") (class "Default")
      (node (ref "U14") (pin "22") (pinfunction "3A7_22") (pintype "bidirectional"))
    )
    (net (code "260") (name "unconnected-(U14B-3A8-Pad23)") (class "Default")
      (node (ref "U14") (pin "23") (pinfunction "3A8_23") (pintype "bidirectional"))
    )
  )
)
